# driver_3KW.net
KiCad netlist of a schematic drawn in EAGLE
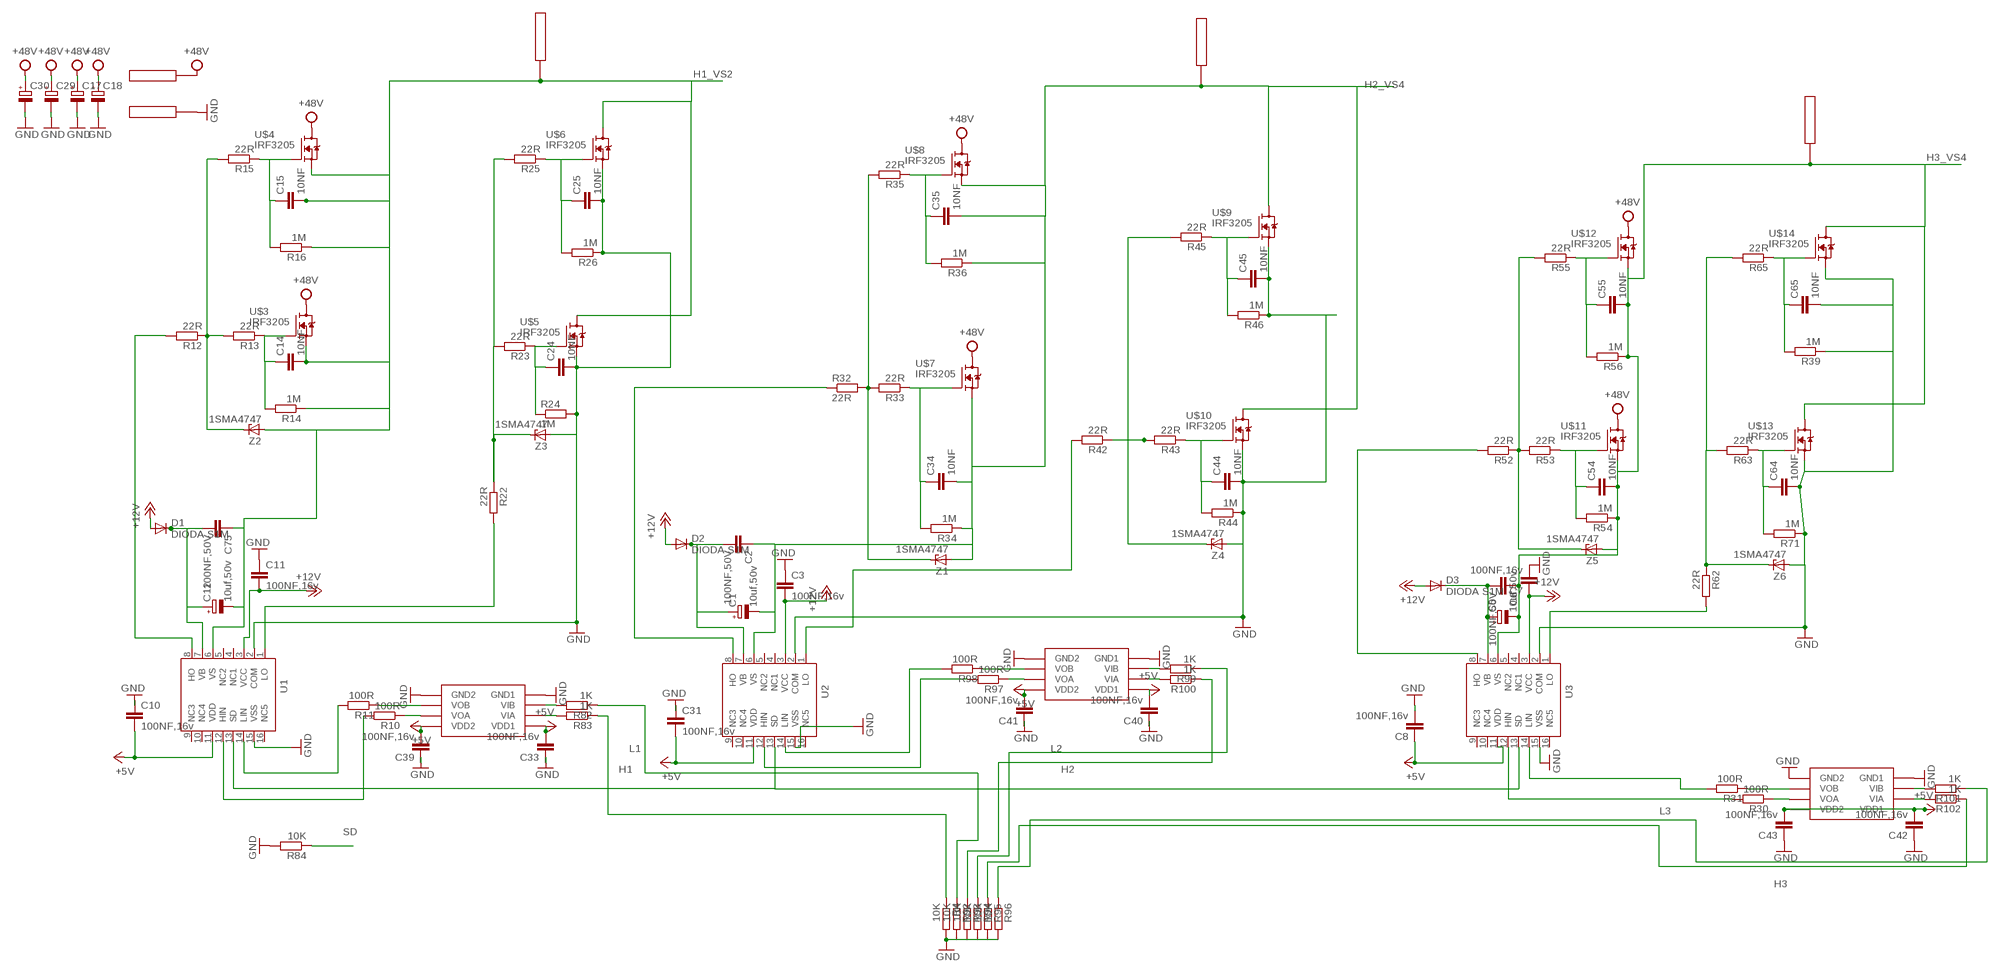
[diagram p0: schematic, sheet 1, part 1 of 2]
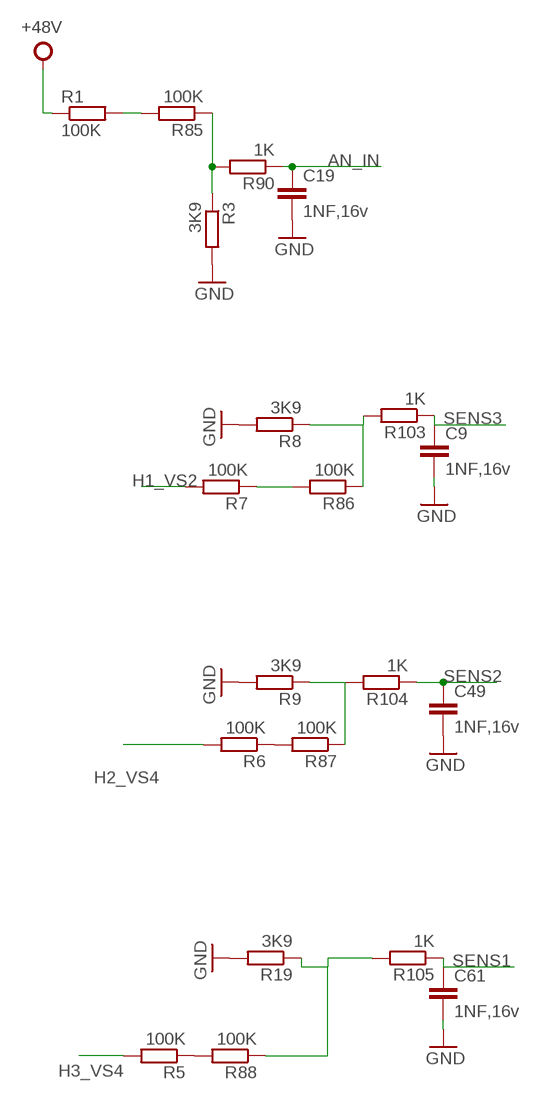
[diagram p1: schematic, sheet 1, part 2 of 2]
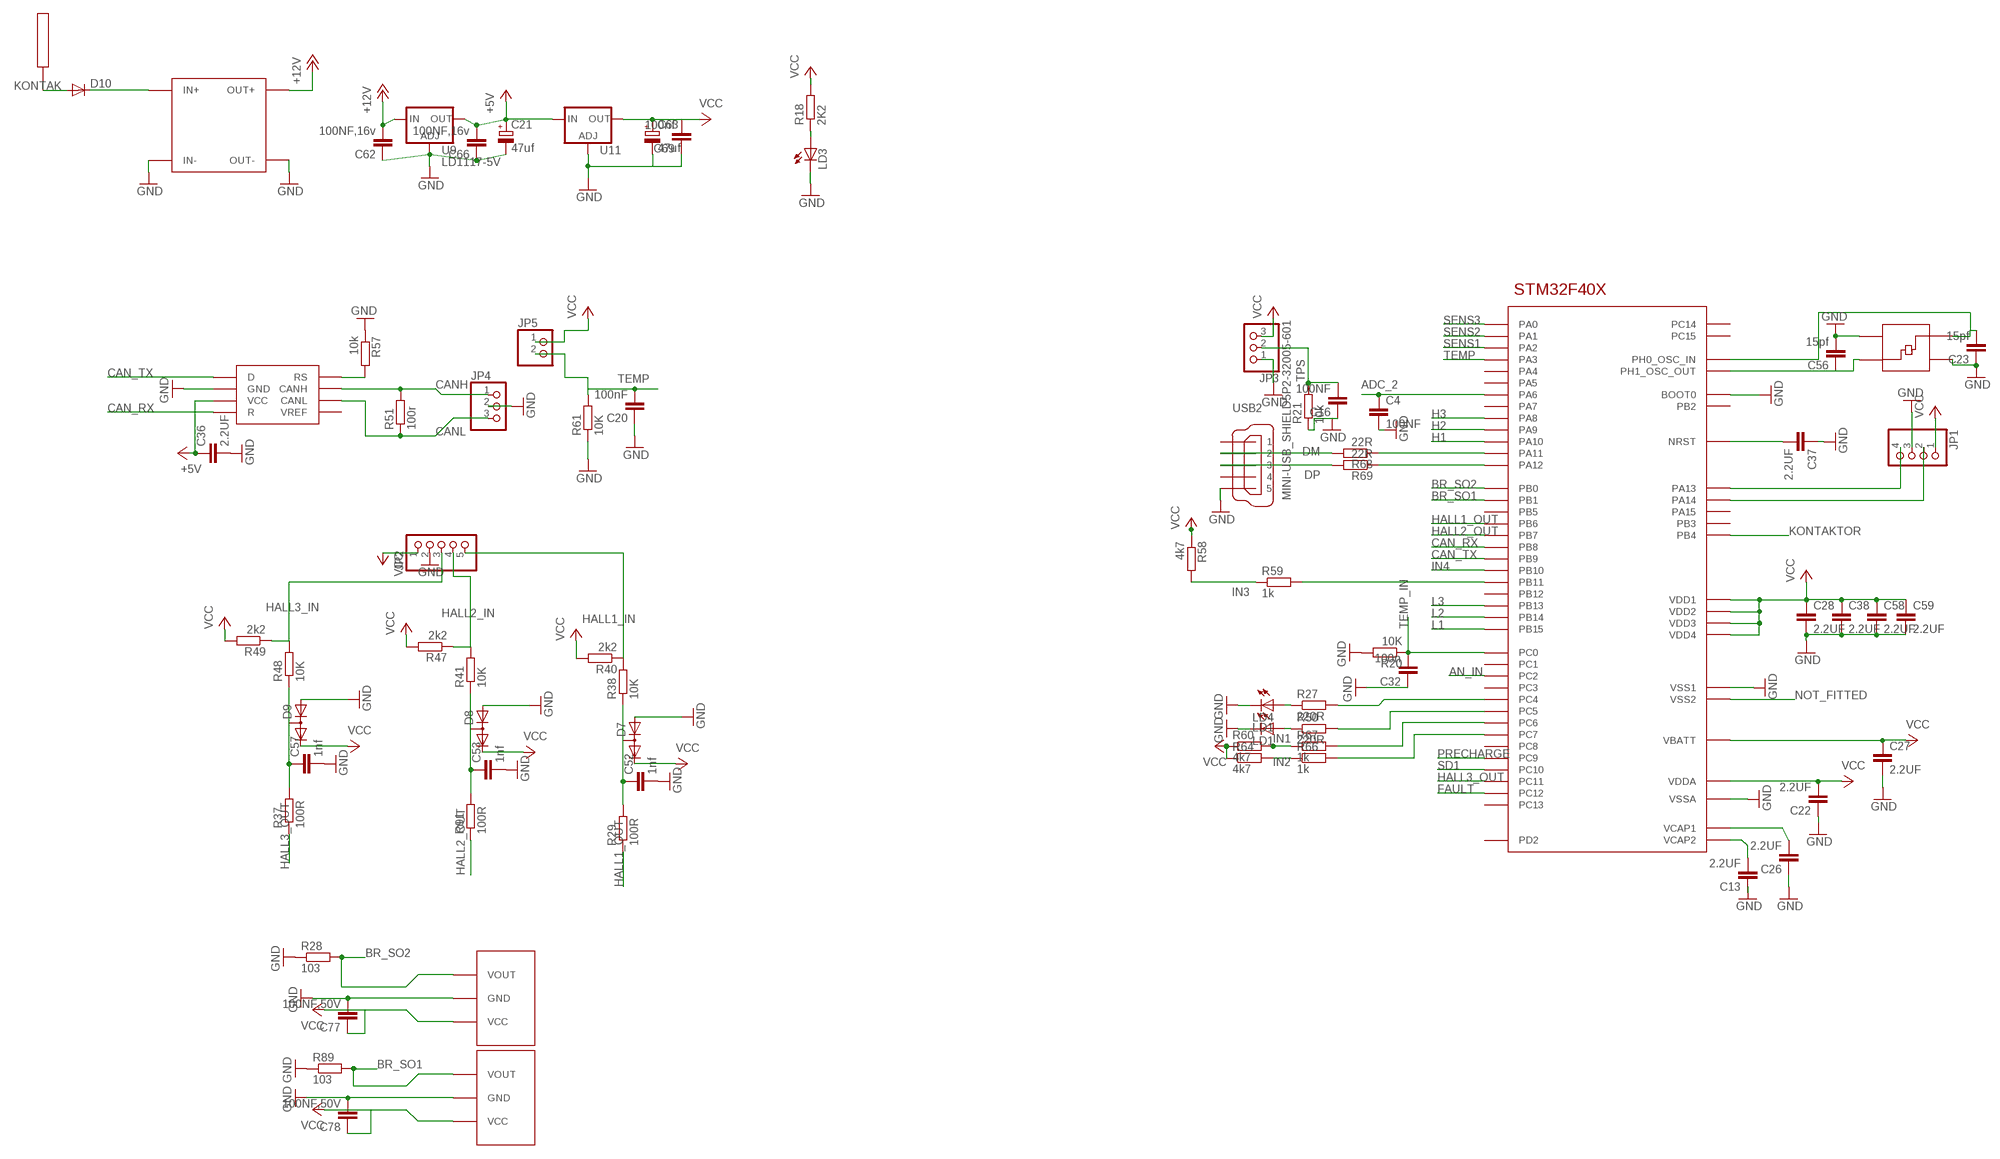
[diagram p2: schematic, sheet 2]

(export (version "E")
  (design (tool "Eeschema 10.0.6"))
  (components
    (comp (ref "C4")
      (value "100NF")
      (footprint "eagle-import:C_0805")
      (libsource (lib "eagle-import") (part "C_0805"))
    )
    (comp (ref "C13")
      (value "2.2UF")
      (footprint "eagle-import:C_0805")
      (libsource (lib "eagle-import") (part "C_0805"))
    )
    (comp (ref "C16")
      (value "100NF")
      (footprint "eagle-import:C_0805")
      (libsource (lib "eagle-import") (part "C_0805"))
    )
    (comp (ref "C20")
      (value "100nF")
      (footprint "eagle-import:C_0805")
      (libsource (lib "eagle-import") (part "C_0805"))
    )
    (comp (ref "C21")
      (value "47uf")
      (footprint "eagle-import:153CLV-0605")
      (libsource (lib "eagle-import") (part "CPOL-EU153CLV-0605"))
    )
    (comp (ref "C22")
      (value "2.2UF")
      (footprint "eagle-import:C_0805")
      (libsource (lib "eagle-import") (part "C_0805"))
    )
    (comp (ref "C23")
      (value "15pf")
      (footprint "eagle-import:C_0805")
      (libsource (lib "eagle-import") (part "C_0805"))
    )
    (comp (ref "C26")
      (value "2.2UF")
      (footprint "eagle-import:C_0805")
      (libsource (lib "eagle-import") (part "C_0805"))
    )
    (comp (ref "C27")
      (value "2.2UF")
      (footprint "eagle-import:C_0805")
      (libsource (lib "eagle-import") (part "C_0805"))
    )
    (comp (ref "C28")
      (value "2.2UF")
      (footprint "eagle-import:C_0805")
      (libsource (lib "eagle-import") (part "C_0805"))
    )
    (comp (ref "C32")
      (value "100n")
      (footprint "eagle-import:C_0805")
      (libsource (lib "eagle-import") (part "C_0805"))
    )
    (comp (ref "C36")
      (value "2.2UF")
      (footprint "eagle-import:C_0805")
      (libsource (lib "eagle-import") (part "C_0805"))
    )
    (comp (ref "C37")
      (value "2.2UF")
      (footprint "eagle-import:C_0805")
      (libsource (lib "eagle-import") (part "C_0805"))
    )
    (comp (ref "C38")
      (value "2.2UF")
      (footprint "eagle-import:C_0805")
      (libsource (lib "eagle-import") (part "C_0805"))
    )
    (comp (ref "C52")
      (value "1nf")
      (footprint "eagle-import:C_0805")
      (libsource (lib "eagle-import") (part "C_0805"))
    )
    (comp (ref "C53")
      (value "1nf")
      (footprint "eagle-import:C_0805")
      (libsource (lib "eagle-import") (part "C_0805"))
    )
    (comp (ref "C56")
      (value "15pf")
      (footprint "eagle-import:C_0805")
      (libsource (lib "eagle-import") (part "C_0805"))
    )
    (comp (ref "C57")
      (value "1nf")
      (footprint "eagle-import:C_0805")
      (libsource (lib "eagle-import") (part "C_0805"))
    )
    (comp (ref "C58")
      (value "2.2UF")
      (footprint "eagle-import:C_0805")
      (libsource (lib "eagle-import") (part "C_0805"))
    )
    (comp (ref "C59")
      (value "2.2UF")
      (footprint "eagle-import:C_0805")
      (libsource (lib "eagle-import") (part "C_0805"))
    )
    (comp (ref "C62")
      (value "100NF,16v")
      (footprint "eagle-import:C_0805")
      (libsource (lib "eagle-import") (part "C_0805"))
    )
    (comp (ref "C63")
      (value "47uf")
      (footprint "eagle-import:153CLV-0605")
      (libsource (lib "eagle-import") (part "CPOL-EU153CLV-0605"))
    )
    (comp (ref "C66")
      (value "100NF,16v")
      (footprint "eagle-import:C_0805")
      (libsource (lib "eagle-import") (part "C_0805"))
    )
    (comp (ref "C69")
      (value "100nf")
      (footprint "eagle-import:C_0805")
      (libsource (lib "eagle-import") (part "C_0805"))
    )
    (comp (ref "C77")
      (value "100NF,50V")
      (footprint "eagle-import:C_0805")
      (libsource (lib "eagle-import") (part "C_0805"))
    )
    (comp (ref "C78")
      (value "100NF,50V")
      (footprint "eagle-import:C_0805")
      (libsource (lib "eagle-import") (part "C_0805"))
    )
    (comp (ref "D7")
      (value "DIODE_2CACA-SOT23")
      (footprint "eagle-import:SOT23")
      (libsource (lib "eagle-import") (part "DIODE_2CACA-SOT23"))
    )
    (comp (ref "D8")
      (value "DIODE_2CACA-SOT23")
      (footprint "eagle-import:SOT23")
      (libsource (lib "eagle-import") (part "DIODE_2CACA-SOT23"))
    )
    (comp (ref "D9")
      (value "DIODE_2CACA-SOT23")
      (footprint "eagle-import:SOT23")
      (libsource (lib "eagle-import") (part "DIODE_2CACA-SOT23"))
    )
    (comp (ref "D10")
      (value "DIODE-SMB")
      (footprint "eagle-import:SMB")
      (libsource (lib "eagle-import") (part "DIODE-SMB"))
    )
    (comp (ref "JP1")
      (value "PINHD-1X4")
      (footprint "eagle-import:1X04")
      (libsource (lib "eagle-import") (part "PINHD-1X4"))
    )
    (comp (ref "JP2")
      (value "PINHD-1X5")
      (footprint "eagle-import:1X05")
      (libsource (lib "eagle-import") (part "PINHD-1X5"))
    )
    (comp (ref "JP3")
      (value "PINHD-1X3")
      (footprint "eagle-import:1X03")
      (libsource (lib "eagle-import") (part "PINHD-1X3"))
    )
    (comp (ref "JP4")
      (value "PINHD-1X3")
      (footprint "eagle-import:1X03")
      (libsource (lib "eagle-import") (part "PINHD-1X3"))
    )
    (comp (ref "JP5")
      (value "PINHD-1X2")
      (footprint "eagle-import:1X02")
      (libsource (lib "eagle-import") (part "PINHD-1X2"))
    )
    (comp (ref "LD1")
      (value "LED3MM")
      (footprint "eagle-import:LED3MM")
      (libsource (lib "eagle-import") (part "LED3MM"))
    )
    (comp (ref "LD3")
      (value "LED3MM")
      (footprint "eagle-import:LED3MM")
      (libsource (lib "eagle-import") (part "LED3MM"))
    )
    (comp (ref "LD4")
      (value "LD1")
      (footprint "eagle-import:LED3MM")
      (libsource (lib "eagle-import") (part "LED3MM"))
    )
    (comp (ref "R18")
      (value "2K2")
      (footprint "eagle-import:R_0805")
      (libsource (lib "eagle-import") (part "R_EU"))
    )
    (comp (ref "R20")
      (value "10K")
      (footprint "eagle-import:R_0805")
      (libsource (lib "eagle-import") (part "R_EU"))
    )
    (comp (ref "R21")
      (value "10k")
      (footprint "eagle-import:R_0805")
      (libsource (lib "eagle-import") (part "R_EU"))
    )
    (comp (ref "R27")
      (value "220R")
      (footprint "eagle-import:R_0805")
      (libsource (lib "eagle-import") (part "R_EU"))
    )
    (comp (ref "R28")
      (value "103")
      (footprint "eagle-import:R_0805")
      (libsource (lib "eagle-import") (part "R_EU"))
    )
    (comp (ref "R29")
      (value "100R")
      (footprint "eagle-import:R_0805")
      (libsource (lib "eagle-import") (part "R_EU"))
    )
    (comp (ref "R37")
      (value "100R")
      (footprint "eagle-import:R_0805")
      (libsource (lib "eagle-import") (part "R_EU"))
    )
    (comp (ref "R38")
      (value "10K")
      (footprint "eagle-import:R_0805")
      (libsource (lib "eagle-import") (part "R_EU"))
    )
    (comp (ref "R40")
      (value "2k2")
      (footprint "eagle-import:R_0805")
      (libsource (lib "eagle-import") (part "R_EU"))
    )
    (comp (ref "R41")
      (value "10K")
      (footprint "eagle-import:R_0805")
      (libsource (lib "eagle-import") (part "R_EU"))
    )
    (comp (ref "R47")
      (value "2k2")
      (footprint "eagle-import:R_0805")
      (libsource (lib "eagle-import") (part "R_EU"))
    )
    (comp (ref "R48")
      (value "10K")
      (footprint "eagle-import:R_0805")
      (libsource (lib "eagle-import") (part "R_EU"))
    )
    (comp (ref "R49")
      (value "2k2")
      (footprint "eagle-import:R_0805")
      (libsource (lib "eagle-import") (part "R_EU"))
    )
    (comp (ref "R50")
      (value "220R")
      (footprint "eagle-import:R_0805")
      (libsource (lib "eagle-import") (part "R_EU"))
    )
    (comp (ref "R51")
      (value "100r")
      (footprint "eagle-import:R_0805")
      (libsource (lib "eagle-import") (part "R_EU"))
    )
    (comp (ref "R57")
      (value "10k")
      (footprint "eagle-import:R_0805")
      (libsource (lib "eagle-import") (part "R_EU"))
    )
    (comp (ref "R58")
      (value "4k7")
      (footprint "eagle-import:R_0805")
      (libsource (lib "eagle-import") (part "R_EU"))
    )
    (comp (ref "R59")
      (value "1k")
      (footprint "eagle-import:R_0805")
      (libsource (lib "eagle-import") (part "R_EU"))
    )
    (comp (ref "R60")
      (value "4k7")
      (footprint "eagle-import:R_0805")
      (libsource (lib "eagle-import") (part "R_EU"))
    )
    (comp (ref "R61")
      (value "10K")
      (footprint "eagle-import:R_0805")
      (libsource (lib "eagle-import") (part "R_EU"))
    )
    (comp (ref "R64")
      (value "4k7")
      (footprint "eagle-import:R_0805")
      (libsource (lib "eagle-import") (part "R_EU"))
    )
    (comp (ref "R66")
      (value "1k")
      (footprint "eagle-import:R_0805")
      (libsource (lib "eagle-import") (part "R_EU"))
    )
    (comp (ref "R67")
      (value "1k")
      (footprint "eagle-import:R_0805")
      (libsource (lib "eagle-import") (part "R_EU"))
    )
    (comp (ref "R68")
      (value "22R")
      (footprint "eagle-import:R_0805")
      (libsource (lib "eagle-import") (part "R_EU"))
    )
    (comp (ref "R69")
      (value "22R")
      (footprint "eagle-import:R_0805")
      (libsource (lib "eagle-import") (part "R_EU"))
    )
    (comp (ref "R89")
      (value "103")
      (footprint "eagle-import:R_0805")
      (libsource (lib "eagle-import") (part "R_EU"))
    )
    (comp (ref "R91")
      (value "100R")
      (footprint "eagle-import:R_0805")
      (libsource (lib "eagle-import") (part "R_EU"))
    )
    (comp (ref "U$1")
      (value "LM2596")
      (footprint "eagle-import:DC-DC")
      (libsource (lib "eagle-import") (part "LM2596"))
    )
    (comp (ref "U$2")
      (value "STM32F40X")
      (footprint "eagle-import:DIP64")
      (libsource (lib "eagle-import") (part "STM32F40X"))
    )
    (comp (ref "U$20")
      (value "L01Z400S05")
      (footprint "eagle-import:L01ZXXXS05")
      (libsource (lib "eagle-import") (part "L01Z400S05"))
    )
    (comp (ref "U$21")
      (value "L01Z400S05")
      (footprint "eagle-import:L01ZXXXS05")
      (libsource (lib "eagle-import") (part "L01Z400S05"))
    )
    (comp (ref "U$22")
      (value "PINOUT")
      (footprint "eagle-import:1DIP")
      (libsource (lib "eagle-import") (part "PINOUT"))
    )
    (comp (ref "U9")
      (value "LD1117-5V")
      (footprint "eagle-import:DPACK@1")
      (libsource (lib "eagle-import") (part "v-reg_LM317?MABDT"))
    )
    (comp (ref "U11")
      (value "LM317MABDT")
      (footprint "eagle-import:DPACK@1")
      (libsource (lib "eagle-import") (part "v-reg_LM317?MABDT"))
    )
    (comp (ref "U73")
      (value "MCP2551")
      (footprint "eagle-import:SN65HVD230")
      (libsource (lib "eagle-import") (part "SN65HVD230"))
    )
    (comp (ref "USB2")
      (value "MINI-USB_SHIELD5P2-32005-601")
      (footprint "eagle-import:32005-601")
      (libsource (lib "eagle-import") (part "MINI-USB_SHIELD5P2-32005-601"))
    )
    (comp (ref "X2")
      (value "UBM")
      (footprint "eagle-import:UBM")
      (libsource (lib "eagle-import") (part "UBM"))
    )
    (comp (ref "C1")
      (value "10uf,50v")
      (footprint "eagle-import:E2,5-5")
      (libsource (lib "eagle-import") (part "CPOL-EUE2.5-5"))
    )
    (comp (ref "C2")
      (value "100NF,50V")
      (footprint "eagle-import:C_0805")
      (libsource (lib "eagle-import") (part "C_0805"))
    )
    (comp (ref "C3")
      (value "100NF,16v")
      (footprint "eagle-import:C_0805")
      (libsource (lib "eagle-import") (part "C_0805"))
    )
    (comp (ref "C5")
      (value "10uf,50v")
      (footprint "eagle-import:E2,5-5")
      (libsource (lib "eagle-import") (part "CPOL-EUE2.5-5"))
    )
    (comp (ref "C6")
      (value "100NF,50V")
      (footprint "eagle-import:C_0805")
      (libsource (lib "eagle-import") (part "C_0805"))
    )
    (comp (ref "C7")
      (value "100NF,16v")
      (footprint "eagle-import:C_0805")
      (libsource (lib "eagle-import") (part "C_0805"))
    )
    (comp (ref "C8")
      (value "100NF,16v")
      (footprint "eagle-import:C_0805")
      (libsource (lib "eagle-import") (part "C_0805"))
    )
    (comp (ref "C9")
      (value "1NF,16v")
      (footprint "eagle-import:C_0805")
      (libsource (lib "eagle-import") (part "C_0805"))
    )
    (comp (ref "C10")
      (value "100NF,16v")
      (footprint "eagle-import:C_0805")
      (libsource (lib "eagle-import") (part "C_0805"))
    )
    (comp (ref "C11")
      (value "100NF,16v")
      (footprint "eagle-import:C_0805")
      (libsource (lib "eagle-import") (part "C_0805"))
    )
    (comp (ref "C12")
      (value "10uf,50v")
      (footprint "eagle-import:E2,5-5")
      (libsource (lib "eagle-import") (part "CPOL-EUE2.5-5"))
    )
    (comp (ref "C14")
      (value "10NF")
      (footprint "eagle-import:C_0805")
      (libsource (lib "eagle-import") (part "C_0805"))
    )
    (comp (ref "C15")
      (value "10NF")
      (footprint "eagle-import:C_0805")
      (libsource (lib "eagle-import") (part "C_0805"))
    )
    (comp (ref "C17")
      (value "CPOL-EUE7.5-16")
      (footprint "eagle-import:E7,5-16")
      (libsource (lib "eagle-import") (part "CPOL-EUE7.5-16"))
    )
    (comp (ref "C18")
      (value "CPOL-EUE7.5-16")
      (footprint "eagle-import:E7,5-16")
      (libsource (lib "eagle-import") (part "CPOL-EUE7.5-16"))
    )
    (comp (ref "C19")
      (value "1NF,16v")
      (footprint "eagle-import:C_0805")
      (libsource (lib "eagle-import") (part "C_0805"))
    )
    (comp (ref "C24")
      (value "10NF")
      (footprint "eagle-import:C_0805")
      (libsource (lib "eagle-import") (part "C_0805"))
    )
    (comp (ref "C25")
      (value "10NF")
      (footprint "eagle-import:C_0805")
      (libsource (lib "eagle-import") (part "C_0805"))
    )
    (comp (ref "C29")
      (value "CPOL-EUE7.5-16")
      (footprint "eagle-import:E7,5-16")
      (libsource (lib "eagle-import") (part "CPOL-EUE7.5-16"))
    )
    (comp (ref "C30")
      (value "CPOL-EUE7.5-16")
      (footprint "eagle-import:E7,5-16")
      (libsource (lib "eagle-import") (part "CPOL-EUE7.5-16"))
    )
    (comp (ref "C31")
      (value "100NF,16v")
      (footprint "eagle-import:C_0805")
      (libsource (lib "eagle-import") (part "C_0805"))
    )
    (comp (ref "C33")
      (value "100NF,16v")
      (footprint "eagle-import:C_0805")
      (libsource (lib "eagle-import") (part "C_0805"))
    )
    (comp (ref "C34")
      (value "10NF")
      (footprint "eagle-import:C_0805")
      (libsource (lib "eagle-import") (part "C_0805"))
    )
    (comp (ref "C35")
      (value "10NF")
      (footprint "eagle-import:C_0805")
      (libsource (lib "eagle-import") (part "C_0805"))
    )
    (comp (ref "C39")
      (value "100NF,16v")
      (footprint "eagle-import:C_0805")
      (libsource (lib "eagle-import") (part "C_0805"))
    )
    (comp (ref "C40")
      (value "100NF,16v")
      (footprint "eagle-import:C_0805")
      (libsource (lib "eagle-import") (part "C_0805"))
    )
    (comp (ref "C41")
      (value "100NF,16v")
      (footprint "eagle-import:C_0805")
      (libsource (lib "eagle-import") (part "C_0805"))
    )
    (comp (ref "C42")
      (value "100NF,16v")
      (footprint "eagle-import:C_0805")
      (libsource (lib "eagle-import") (part "C_0805"))
    )
    (comp (ref "C43")
      (value "100NF,16v")
      (footprint "eagle-import:C_0805")
      (libsource (lib "eagle-import") (part "C_0805"))
    )
    (comp (ref "C44")
      (value "10NF")
      (footprint "eagle-import:C_0805")
      (libsource (lib "eagle-import") (part "C_0805"))
    )
    (comp (ref "C45")
      (value "10NF")
      (footprint "eagle-import:C_0805")
      (libsource (lib "eagle-import") (part "C_0805"))
    )
    (comp (ref "C49")
      (value "1NF,16v")
      (footprint "eagle-import:C_0805")
      (libsource (lib "eagle-import") (part "C_0805"))
    )
    (comp (ref "C54")
      (value "10NF")
      (footprint "eagle-import:C_0805")
      (libsource (lib "eagle-import") (part "C_0805"))
    )
    (comp (ref "C55")
      (value "10NF")
      (footprint "eagle-import:C_0805")
      (libsource (lib "eagle-import") (part "C_0805"))
    )
    (comp (ref "C61")
      (value "1NF,16v")
      (footprint "eagle-import:C_0805")
      (libsource (lib "eagle-import") (part "C_0805"))
    )
    (comp (ref "C64")
      (value "10NF")
      (footprint "eagle-import:C_0805")
      (libsource (lib "eagle-import") (part "C_0805"))
    )
    (comp (ref "C65")
      (value "10NF")
      (footprint "eagle-import:C_0805")
      (libsource (lib "eagle-import") (part "C_0805"))
    )
    (comp (ref "C75")
      (value "100NF,50V")
      (footprint "eagle-import:C_0805")
      (libsource (lib "eagle-import") (part "C_0805"))
    )
    (comp (ref "D1")
      (value "DIODA S1M")
      (footprint "eagle-import:DO-214AC")
      (libsource (lib "eagle-import") (part "DIODE-DO-214AC"))
    )
    (comp (ref "D2")
      (value "DIODA S1M")
      (footprint "eagle-import:DO-214AC")
      (libsource (lib "eagle-import") (part "DIODE-DO-214AC"))
    )
    (comp (ref "D3")
      (value "DIODA S1M")
      (footprint "eagle-import:DO-214AC")
      (libsource (lib "eagle-import") (part "DIODE-DO-214AC"))
    )
    (comp (ref "R1")
      (value "100K")
      (footprint "eagle-import:1206X")
      (libsource (lib "eagle-import") (part "R-EU_R1206X"))
    )
    (comp (ref "R3")
      (value "3K9")
      (footprint "eagle-import:1206X")
      (libsource (lib "eagle-import") (part "R-EU_R1206X"))
    )
    (comp (ref "R4")
      (value "10K")
      (footprint "eagle-import:R_0805")
      (libsource (lib "eagle-import") (part "R_EU"))
    )
    (comp (ref "R5")
      (value "100K")
      (footprint "eagle-import:1206X")
      (libsource (lib "eagle-import") (part "R-EU_R1206X"))
    )
    (comp (ref "R6")
      (value "100K")
      (footprint "eagle-import:1206X")
      (libsource (lib "eagle-import") (part "R-EU_R1206X"))
    )
    (comp (ref "R7")
      (value "100K")
      (footprint "eagle-import:1206X")
      (libsource (lib "eagle-import") (part "R-EU_R1206X"))
    )
    (comp (ref "R8")
      (value "3K9")
      (footprint "eagle-import:1206X")
      (libsource (lib "eagle-import") (part "R-EU_R1206X"))
    )
    (comp (ref "R9")
      (value "3K9")
      (footprint "eagle-import:1206X")
      (libsource (lib "eagle-import") (part "R-EU_R1206X"))
    )
    (comp (ref "R10")
      (value "100R")
      (footprint "eagle-import:R_0805")
      (libsource (lib "eagle-import") (part "R_EU"))
    )
    (comp (ref "R11")
      (value "100R")
      (footprint "eagle-import:R_0805")
      (libsource (lib "eagle-import") (part "R_EU"))
    )
    (comp (ref "R12")
      (value "22R")
      (footprint "eagle-import:1210X")
      (libsource (lib "eagle-import") (part "R-EU_1210X"))
    )
    (comp (ref "R13")
      (value "22R")
      (footprint "eagle-import:1210X")
      (libsource (lib "eagle-import") (part "R-EU_1210X"))
    )
    (comp (ref "R14")
      (value "1M")
      (footprint "eagle-import:1206X")
      (libsource (lib "eagle-import") (part "R-EU_R1206X"))
    )
    (comp (ref "R15")
      (value "22R")
      (footprint "eagle-import:1210X")
      (libsource (lib "eagle-import") (part "R-EU_1210X"))
    )
    (comp (ref "R16")
      (value "1M")
      (footprint "eagle-import:1206X")
      (libsource (lib "eagle-import") (part "R-EU_R1206X"))
    )
    (comp (ref "R19")
      (value "3K9")
      (footprint "eagle-import:1206X")
      (libsource (lib "eagle-import") (part "R-EU_R1206X"))
    )
    (comp (ref "R22")
      (value "22R")
      (footprint "eagle-import:1210X")
      (libsource (lib "eagle-import") (part "R-EU_1210X"))
    )
    (comp (ref "R23")
      (value "22R")
      (footprint "eagle-import:1210X")
      (libsource (lib "eagle-import") (part "R-EU_1210X"))
    )
    (comp (ref "R24")
      (value "1M")
      (footprint "eagle-import:1206X")
      (libsource (lib "eagle-import") (part "R-EU_R1206X"))
    )
    (comp (ref "R25")
      (value "22R")
      (footprint "eagle-import:1210X")
      (libsource (lib "eagle-import") (part "R-EU_1210X"))
    )
    (comp (ref "R26")
      (value "1M")
      (footprint "eagle-import:1206X")
      (libsource (lib "eagle-import") (part "R-EU_R1206X"))
    )
    (comp (ref "R30")
      (value "100R")
      (footprint "eagle-import:R_0805")
      (libsource (lib "eagle-import") (part "R_EU"))
    )
    (comp (ref "R31")
      (value "100R")
      (footprint "eagle-import:R_0805")
      (libsource (lib "eagle-import") (part "R_EU"))
    )
    (comp (ref "R32")
      (value "22R")
      (footprint "eagle-import:1210X")
      (libsource (lib "eagle-import") (part "R-EU_1210X"))
    )
    (comp (ref "R33")
      (value "22R")
      (footprint "eagle-import:1210X")
      (libsource (lib "eagle-import") (part "R-EU_1210X"))
    )
    (comp (ref "R34")
      (value "1M")
      (footprint "eagle-import:1206X")
      (libsource (lib "eagle-import") (part "R-EU_R1206X"))
    )
    (comp (ref "R35")
      (value "22R")
      (footprint "eagle-import:1210X")
      (libsource (lib "eagle-import") (part "R-EU_1210X"))
    )
    (comp (ref "R36")
      (value "1M")
      (footprint "eagle-import:1206X")
      (libsource (lib "eagle-import") (part "R-EU_R1206X"))
    )
    (comp (ref "R39")
      (value "1M")
      (footprint "eagle-import:1206X")
      (libsource (lib "eagle-import") (part "R-EU_R1206X"))
    )
    (comp (ref "R42")
      (value "22R")
      (footprint "eagle-import:1210X")
      (libsource (lib "eagle-import") (part "R-EU_1210X"))
    )
    (comp (ref "R43")
      (value "22R")
      (footprint "eagle-import:1210X")
      (libsource (lib "eagle-import") (part "R-EU_1210X"))
    )
    (comp (ref "R44")
      (value "1M")
      (footprint "eagle-import:1206X")
      (libsource (lib "eagle-import") (part "R-EU_R1206X"))
    )
    (comp (ref "R45")
      (value "22R")
      (footprint "eagle-import:1210X")
      (libsource (lib "eagle-import") (part "R-EU_1210X"))
    )
    (comp (ref "R46")
      (value "1M")
      (footprint "eagle-import:1206X")
      (libsource (lib "eagle-import") (part "R-EU_R1206X"))
    )
    (comp (ref "R52")
      (value "22R")
      (footprint "eagle-import:1210X")
      (libsource (lib "eagle-import") (part "R-EU_1210X"))
    )
    (comp (ref "R53")
      (value "22R")
      (footprint "eagle-import:1210X")
      (libsource (lib "eagle-import") (part "R-EU_1210X"))
    )
    (comp (ref "R54")
      (value "1M")
      (footprint "eagle-import:1206X")
      (libsource (lib "eagle-import") (part "R-EU_R1206X"))
    )
    (comp (ref "R55")
      (value "22R")
      (footprint "eagle-import:1210X")
      (libsource (lib "eagle-import") (part "R-EU_1210X"))
    )
    (comp (ref "R56")
      (value "1M")
      (footprint "eagle-import:1206X")
      (libsource (lib "eagle-import") (part "R-EU_R1206X"))
    )
    (comp (ref "R62")
      (value "22R")
      (footprint "eagle-import:1210X")
      (libsource (lib "eagle-import") (part "R-EU_1210X"))
    )
    (comp (ref "R63")
      (value "22R")
      (footprint "eagle-import:1210X")
      (libsource (lib "eagle-import") (part "R-EU_1210X"))
    )
    (comp (ref "R65")
      (value "22R")
      (footprint "eagle-import:1210X")
      (libsource (lib "eagle-import") (part "R-EU_1210X"))
    )
    (comp (ref "R71")
      (value "1M")
      (footprint "eagle-import:1206X")
      (libsource (lib "eagle-import") (part "R-EU_R1206X"))
    )
    (comp (ref "R82")
      (value "1K")
      (footprint "eagle-import:R_0805")
      (libsource (lib "eagle-import") (part "R_EU"))
    )
    (comp (ref "R83")
      (value "1K")
      (footprint "eagle-import:R_0805")
      (libsource (lib "eagle-import") (part "R_EU"))
    )
    (comp (ref "R84")
      (value "10K")
      (footprint "eagle-import:R_0805")
      (libsource (lib "eagle-import") (part "R_EU"))
    )
    (comp (ref "R85")
      (value "100K")
      (footprint "eagle-import:1206X")
      (libsource (lib "eagle-import") (part "R-EU_R1206X"))
    )
    (comp (ref "R86")
      (value "100K")
      (footprint "eagle-import:1206X")
      (libsource (lib "eagle-import") (part "R-EU_R1206X"))
    )
    (comp (ref "R87")
      (value "100K")
      (footprint "eagle-import:1206X")
      (libsource (lib "eagle-import") (part "R-EU_R1206X"))
    )
    (comp (ref "R88")
      (value "100K")
      (footprint "eagle-import:1206X")
      (libsource (lib "eagle-import") (part "R-EU_R1206X"))
    )
    (comp (ref "R90")
      (value "1K")
      (footprint "eagle-import:1206X")
      (libsource (lib "eagle-import") (part "R-EU_R1206X"))
    )
    (comp (ref "R92")
      (value "10K")
      (footprint "eagle-import:R_0805")
      (libsource (lib "eagle-import") (part "R_EU"))
    )
    (comp (ref "R93")
      (value "10K")
      (footprint "eagle-import:R_0805")
      (libsource (lib "eagle-import") (part "R_EU"))
    )
    (comp (ref "R94")
      (value "10K")
      (footprint "eagle-import:R_0805")
      (libsource (lib "eagle-import") (part "R_EU"))
    )
    (comp (ref "R95")
      (value "10K")
      (footprint "eagle-import:R_0805")
      (libsource (lib "eagle-import") (part "R_EU"))
    )
    (comp (ref "R96")
      (value "10K")
      (footprint "eagle-import:R_0805")
      (libsource (lib "eagle-import") (part "R_EU"))
    )
    (comp (ref "R97")
      (value "100R")
      (footprint "eagle-import:R_0805")
      (libsource (lib "eagle-import") (part "R_EU"))
    )
    (comp (ref "R98")
      (value "100R")
      (footprint "eagle-import:R_0805")
      (libsource (lib "eagle-import") (part "R_EU"))
    )
    (comp (ref "R99")
      (value "1K")
      (footprint "eagle-import:R_0805")
      (libsource (lib "eagle-import") (part "R_EU"))
    )
    (comp (ref "R100")
      (value "1K")
      (footprint "eagle-import:R_0805")
      (libsource (lib "eagle-import") (part "R_EU"))
    )
    (comp (ref "R101")
      (value "1K")
      (footprint "eagle-import:R_0805")
      (libsource (lib "eagle-import") (part "R_EU"))
    )
    (comp (ref "R102")
      (value "1K")
      (footprint "eagle-import:R_0805")
      (libsource (lib "eagle-import") (part "R_EU"))
    )
    (comp (ref "R103")
      (value "1K")
      (footprint "eagle-import:1206X")
      (libsource (lib "eagle-import") (part "R-EU_R1206X"))
    )
    (comp (ref "R104")
      (value "1K")
      (footprint "eagle-import:1206X")
      (libsource (lib "eagle-import") (part "R-EU_R1206X"))
    )
    (comp (ref "R105")
      (value "1K")
      (footprint "eagle-import:1206X")
      (libsource (lib "eagle-import") (part "R-EU_R1206X"))
    )
    (comp (ref "U$3")
      (value "IRF3205")
      (footprint "eagle-import:TO220AB")
      (libsource (lib "eagle-import") (part "IRF3205"))
    )
    (comp (ref "U$4")
      (value "IRF3205")
      (footprint "eagle-import:TO220AB")
      (libsource (lib "eagle-import") (part "IRF3205"))
    )
    (comp (ref "U$5")
      (value "IRF3205")
      (footprint "eagle-import:TO220AB")
      (libsource (lib "eagle-import") (part "IRF3205"))
    )
    (comp (ref "U$6")
      (value "IRF3205")
      (footprint "eagle-import:TO220AB")
      (libsource (lib "eagle-import") (part "IRF3205"))
    )
    (comp (ref "U$7")
      (value "IRF3205")
      (footprint "eagle-import:TO220AB")
      (libsource (lib "eagle-import") (part "IRF3205"))
    )
    (comp (ref "U$8")
      (value "IRF3205")
      (footprint "eagle-import:TO220AB")
      (libsource (lib "eagle-import") (part "IRF3205"))
    )
    (comp (ref "U$9")
      (value "IRF3205")
      (footprint "eagle-import:TO220AB")
      (libsource (lib "eagle-import") (part "IRF3205"))
    )
    (comp (ref "U$10")
      (value "IRF3205")
      (footprint "eagle-import:TO220AB")
      (libsource (lib "eagle-import") (part "IRF3205"))
    )
    (comp (ref "U$11")
      (value "IRF3205")
      (footprint "eagle-import:TO220AB")
      (libsource (lib "eagle-import") (part "IRF3205"))
    )
    (comp (ref "U$12")
      (value "IRF3205")
      (footprint "eagle-import:TO220AB")
      (libsource (lib "eagle-import") (part "IRF3205"))
    )
    (comp (ref "U$13")
      (value "IRF3205")
      (footprint "eagle-import:TO220AB")
      (libsource (lib "eagle-import") (part "IRF3205"))
    )
    (comp (ref "U$14")
      (value "IRF3205")
      (footprint "eagle-import:TO220AB")
      (libsource (lib "eagle-import") (part "IRF3205"))
    )
    (comp (ref "U$15")
      (value "PINOUT")
      (footprint "eagle-import:1DIP")
      (libsource (lib "eagle-import") (part "PINOUT"))
    )
    (comp (ref "U$16")
      (value "PINOUT")
      (footprint "eagle-import:1DIP")
      (libsource (lib "eagle-import") (part "PINOUT"))
    )
    (comp (ref "U$17")
      (value "PINOUT")
      (footprint "eagle-import:1DIP")
      (libsource (lib "eagle-import") (part "PINOUT"))
    )
    (comp (ref "U$18")
      (value "PINOUT")
      (footprint "eagle-import:1DIP")
      (libsource (lib "eagle-import") (part "PINOUT"))
    )
    (comp (ref "U$19")
      (value "PINOUT")
      (footprint "eagle-import:1DIP")
      (libsource (lib "eagle-import") (part "PINOUT"))
    )
    (comp (ref "U1")
      (value "IRS2110")
      (footprint "eagle-import:SO16L")
      (libsource (lib "eagle-import") (part "MAX304WE3C"))
    )
    (comp (ref "U2")
      (value "IRS2110")
      (footprint "eagle-import:SO16L")
      (libsource (lib "eagle-import") (part "MAX304WE3C"))
    )
    (comp (ref "U3")
      (value "IRS2110")
      (footprint "eagle-import:SO16L")
      (libsource (lib "eagle-import") (part "MAX304WE3C"))
    )
    (comp (ref "U4")
      (value "ADUM1200")
      (footprint "eagle-import:SO8")
      (libsource (lib "eagle-import") (part "ADUM1200"))
    )
    (comp (ref "U5")
      (value "ADUM1200")
      (footprint "eagle-import:SO8")
      (libsource (lib "eagle-import") (part "ADUM1200"))
    )
    (comp (ref "U6")
      (value "ADUM1200")
      (footprint "eagle-import:SO8")
      (libsource (lib "eagle-import") (part "ADUM1200"))
    )
    (comp (ref "Z1")
      (value "1SMA4747")
      (footprint "eagle-import:SOD80C@1")
      (libsource (lib "eagle-import") (part "ZENER-DIODESOD80C"))
    )
    (comp (ref "Z2")
      (value "1SMA4747")
      (footprint "eagle-import:SOD80C@1")
      (libsource (lib "eagle-import") (part "ZENER-DIODESOD80C"))
    )
    (comp (ref "Z3")
      (value "1SMA4747")
      (footprint "eagle-import:SOD80C@1")
      (libsource (lib "eagle-import") (part "ZENER-DIODESOD80C"))
    )
    (comp (ref "Z4")
      (value "1SMA4747")
      (footprint "eagle-import:SOD80C@1")
      (libsource (lib "eagle-import") (part "ZENER-DIODESOD80C"))
    )
    (comp (ref "Z5")
      (value "1SMA4747")
      (footprint "eagle-import:SOD80C@1")
      (libsource (lib "eagle-import") (part "ZENER-DIODESOD80C"))
    )
    (comp (ref "Z6")
      (value "1SMA4747")
      (footprint "eagle-import:SOD80C@1")
      (libsource (lib "eagle-import") (part "ZENER-DIODESOD80C"))
    )
  )
  (nets
    (net (code "1") (name "+5V") (class "Default")
      (node (ref "C10") (pin "2") (pinfunction "2_2") (pintype "passive"))
      (node (ref "C21") (pin "+") (pinfunction "+_+") (pintype "passive"))
      (node (ref "C31") (pin "2") (pinfunction "2_2") (pintype "passive"))
      (node (ref "C33") (pin "2") (pinfunction "2_2") (pintype "passive"))
      (node (ref "C36") (pin "1") (pinfunction "1_1") (pintype "passive"))
      (node (ref "C39") (pin "2") (pinfunction "2_2") (pintype "passive"))
      (node (ref "C40") (pin "2") (pinfunction "2_2") (pintype "passive"))
      (node (ref "C41") (pin "2") (pinfunction "2_2") (pintype "passive"))
      (node (ref "C42") (pin "2") (pinfunction "2_2") (pintype "passive"))
      (node (ref "C43") (pin "2") (pinfunction "2_2") (pintype "passive"))
      (node (ref "C66") (pin "2") (pinfunction "2_2") (pintype "passive"))
      (node (ref "C8") (pin "1") (pinfunction "1_1") (pintype "passive"))
      (node (ref "U1") (pin "11") (pinfunction "VDD_11") (pintype "output"))
      (node (ref "U11") (pin "3") (pinfunction "IN_3") (pintype "input"))
      (node (ref "U2") (pin "11") (pinfunction "VDD_11") (pintype "output"))
      (node (ref "U3") (pin "11") (pinfunction "VDD_11") (pintype "output"))
      (node (ref "U4") (pin "1") (pinfunction "VDD1_1") (pintype "bidirectional"))
      (node (ref "U4") (pin "8") (pinfunction "VDD2_8") (pintype "bidirectional"))
      (node (ref "U5") (pin "1") (pinfunction "VDD1_1") (pintype "bidirectional"))
      (node (ref "U5") (pin "8") (pinfunction "VDD2_8") (pintype "bidirectional"))
      (node (ref "U6") (pin "1") (pinfunction "VDD1_1") (pintype "bidirectional"))
      (node (ref "U6") (pin "8") (pinfunction "VDD2_8") (pintype "bidirectional"))
      (node (ref "U73") (pin "P$3") (pinfunction "VCC_P$3") (pintype "bidirectional"))
      (node (ref "U9") (pin "4") (pinfunction "OUT_4") (pintype "passive"))
    )
    (net (code "2") (name "+12V") (class "Default")
      (node (ref "C11") (pin "2") (pinfunction "2_2") (pintype "passive"))
      (node (ref "C3") (pin "2") (pinfunction "2_2") (pintype "passive"))
      (node (ref "C62") (pin "2") (pinfunction "2_2") (pintype "passive"))
      (node (ref "C7") (pin "1") (pinfunction "1_1") (pintype "passive"))
      (node (ref "D1") (pin "A") (pinfunction "A_A") (pintype "passive"))
      (node (ref "D2") (pin "A") (pinfunction "A_A") (pintype "passive"))
      (node (ref "D3") (pin "A") (pinfunction "A_A") (pintype "passive"))
      (node (ref "U$1") (pin "OUT+") (pinfunction "OUT+_OUT+") (pintype "bidirectional"))
      (node (ref "U1") (pin "3") (pinfunction "VCC_3") (pintype "output"))
      (node (ref "U2") (pin "3") (pinfunction "VCC_3") (pintype "output"))
      (node (ref "U3") (pin "3") (pinfunction "VCC_3") (pintype "output"))
      (node (ref "U9") (pin "3") (pinfunction "IN_3") (pintype "input"))
    )
    (net (code "3") (name "+48V") (class "Default")
      (node (ref "C17") (pin "+") (pinfunction "+_+") (pintype "passive"))
      (node (ref "C18") (pin "+") (pinfunction "+_+") (pintype "passive"))
      (node (ref "C29") (pin "+") (pinfunction "+_+") (pintype "passive"))
      (node (ref "C30") (pin "+") (pinfunction "+_+") (pintype "passive"))
      (node (ref "R1") (pin "P$1") (pinfunction "1_P$1") (pintype "passive"))
      (node (ref "U$11") (pin "D") (pinfunction "D_D") (pintype "passive"))
      (node (ref "U$12") (pin "D") (pinfunction "D_D") (pintype "passive"))
      (node (ref "U$18") (pin "P$1") (pinfunction "P$1_P$1") (pintype "bidirectional"))
      (node (ref "U$3") (pin "D") (pinfunction "D_D") (pintype "passive"))
      (node (ref "U$4") (pin "D") (pinfunction "D_D") (pintype "passive"))
      (node (ref "U$7") (pin "D") (pinfunction "D_D") (pintype "passive"))
      (node (ref "U$8") (pin "D") (pinfunction "D_D") (pintype "passive"))
    )
    (net (code "4") (name "ADC_2") (class "Default")
      (node (ref "C4") (pin "1") (pinfunction "1_1") (pintype "passive"))
      (node (ref "U$2") (pin "P$31") (pinfunction "PA6_P$31") (pintype "bidirectional"))
    )
    (net (code "5") (name "AN_IN") (class "Default")
      (node (ref "C19") (pin "1") (pinfunction "1_1") (pintype "passive"))
      (node (ref "R90") (pin "P$1") (pinfunction "1_P$1") (pintype "passive"))
      (node (ref "U$2") (pin "P$10") (pinfunction "PC2_P$10") (pintype "bidirectional"))
    )
    (net (code "6") (name "BR_SO1") (class "Default")
      (node (ref "R89") (pin "2") (pinfunction "2_2") (pintype "passive"))
      (node (ref "U$2") (pin "P$36") (pinfunction "PB1_P$36") (pintype "bidirectional"))
      (node (ref "U$21") (pin "1") (pinfunction "VOUT_1") (pintype "bidirectional"))
    )
    (net (code "7") (name "BR_SO2") (class "Default")
      (node (ref "R28") (pin "2") (pinfunction "2_2") (pintype "passive"))
      (node (ref "U$2") (pin "P$35") (pinfunction "PB0_P$35") (pintype "bidirectional"))
      (node (ref "U$20") (pin "1") (pinfunction "VOUT_1") (pintype "bidirectional"))
    )
    (net (code "8") (name "CANH") (class "Default")
      (node (ref "JP4") (pin "1") (pinfunction "1_1") (pintype "passive"))
      (node (ref "R51") (pin "2") (pinfunction "2_2") (pintype "passive"))
      (node (ref "U73") (pin "P$7") (pinfunction "CANH_P$7") (pintype "bidirectional"))
    )
    (net (code "9") (name "CANL") (class "Default")
      (node (ref "JP4") (pin "3") (pinfunction "3_3") (pintype "passive"))
      (node (ref "R51") (pin "1") (pinfunction "1_1") (pintype "passive"))
      (node (ref "U73") (pin "P$6") (pinfunction "CANL_P$6") (pintype "bidirectional"))
    )
    (net (code "10") (name "CAN_RX") (class "Default")
      (node (ref "U$2") (pin "P$97") (pinfunction "PB8_P$97") (pintype "bidirectional"))
      (node (ref "U73") (pin "P$4") (pinfunction "R_P$4") (pintype "bidirectional"))
    )
    (net (code "11") (name "CAN_TX") (class "Default")
      (node (ref "U$2") (pin "P$98") (pinfunction "PB9_P$98") (pintype "bidirectional"))
      (node (ref "U73") (pin "P$1") (pinfunction "D_P$1") (pintype "bidirectional"))
    )
    (net (code "12") (name "DM") (class "Default")
      (node (ref "R68") (pin "2") (pinfunction "2_2") (pintype "passive"))
      (node (ref "USB2") (pin "2") (pinfunction "2_2") (pintype "passive"))
    )
    (net (code "13") (name "DP") (class "Default")
      (node (ref "R69") (pin "2") (pinfunction "2_2") (pintype "passive"))
      (node (ref "USB2") (pin "3") (pinfunction "3_3") (pintype "passive"))
    )
    (net (code "14") (name "FAULT") (class "Default")
      (node (ref "U$2") (pin "P$89") (pinfunction "PC12_P$89") (pintype "bidirectional"))
    )
    (net (code "15") (name "GND") (class "Default")
      (node (ref "C10") (pin "1") (pinfunction "1_1") (pintype "passive"))
      (node (ref "C11") (pin "1") (pinfunction "1_1") (pintype "passive"))
      (node (ref "C13") (pin "1") (pinfunction "1_1") (pintype "passive"))
      (node (ref "C16") (pin "1") (pinfunction "1_1") (pintype "passive"))
      (node (ref "C17") (pin "-") (pinfunction "-_-") (pintype "passive"))
      (node (ref "C18") (pin "-") (pinfunction "-_-") (pintype "passive"))
      (node (ref "C19") (pin "2") (pinfunction "2_2") (pintype "passive"))
      (node (ref "C20") (pin "1") (pinfunction "1_1") (pintype "passive"))
      (node (ref "C21") (pin "-") (pinfunction "-_-") (pintype "passive"))
      (node (ref "C22") (pin "1") (pinfunction "1_1") (pintype "passive"))
      (node (ref "C23") (pin "1") (pinfunction "1_1") (pintype "passive"))
      (node (ref "C24") (pin "2") (pinfunction "2_2") (pintype "passive"))
      (node (ref "C25") (pin "2") (pinfunction "2_2") (pintype "passive"))
      (node (ref "C26") (pin "1") (pinfunction "1_1") (pintype "passive"))
      (node (ref "C27") (pin "2") (pinfunction "2_2") (pintype "passive"))
      (node (ref "C28") (pin "2") (pinfunction "2_2") (pintype "passive"))
      (node (ref "C29") (pin "-") (pinfunction "-_-") (pintype "passive"))
      (node (ref "C3") (pin "1") (pinfunction "1_1") (pintype "passive"))
      (node (ref "C30") (pin "-") (pinfunction "-_-") (pintype "passive"))
      (node (ref "C31") (pin "1") (pinfunction "1_1") (pintype "passive"))
      (node (ref "C32") (pin "1") (pinfunction "1_1") (pintype "passive"))
      (node (ref "C33") (pin "1") (pinfunction "1_1") (pintype "passive"))
      (node (ref "C36") (pin "2") (pinfunction "2_2") (pintype "passive"))
      (node (ref "C37") (pin "1") (pinfunction "1_1") (pintype "passive"))
      (node (ref "C38") (pin "2") (pinfunction "2_2") (pintype "passive"))
      (node (ref "C39") (pin "1") (pinfunction "1_1") (pintype "passive"))
      (node (ref "C4") (pin "2") (pinfunction "2_2") (pintype "passive"))
      (node (ref "C40") (pin "1") (pinfunction "1_1") (pintype "passive"))
      (node (ref "C41") (pin "1") (pinfunction "1_1") (pintype "passive"))
      (node (ref "C42") (pin "1") (pinfunction "1_1") (pintype "passive"))
      (node (ref "C43") (pin "1") (pinfunction "1_1") (pintype "passive"))
      (node (ref "C44") (pin "2") (pinfunction "2_2") (pintype "passive"))
      (node (ref "C45") (pin "2") (pinfunction "2_2") (pintype "passive"))
      (node (ref "C49") (pin "2") (pinfunction "2_2") (pintype "passive"))
      (node (ref "C52") (pin "2") (pinfunction "2_2") (pintype "passive"))
      (node (ref "C53") (pin "2") (pinfunction "2_2") (pintype "passive"))
      (node (ref "C56") (pin "2") (pinfunction "2_2") (pintype "passive"))
      (node (ref "C57") (pin "2") (pinfunction "2_2") (pintype "passive"))
      (node (ref "C58") (pin "2") (pinfunction "2_2") (pintype "passive"))
      (node (ref "C59") (pin "2") (pinfunction "2_2") (pintype "passive"))
      (node (ref "C61") (pin "2") (pinfunction "2_2") (pintype "passive"))
      (node (ref "C62") (pin "1") (pinfunction "1_1") (pintype "passive"))
      (node (ref "C63") (pin "-") (pinfunction "-_-") (pintype "passive"))
      (node (ref "C64") (pin "2") (pinfunction "2_2") (pintype "passive"))
      (node (ref "C65") (pin "2") (pinfunction "2_2") (pintype "passive"))
      (node (ref "C66") (pin "1") (pinfunction "1_1") (pintype "passive"))
      (node (ref "C69") (pin "1") (pinfunction "1_1") (pintype "passive"))
      (node (ref "C7") (pin "2") (pinfunction "2_2") (pintype "passive"))
      (node (ref "C77") (pin "2") (pinfunction "2_2") (pintype "passive"))
      (node (ref "C78") (pin "2") (pinfunction "2_2") (pintype "passive"))
      (node (ref "C8") (pin "2") (pinfunction "2_2") (pintype "passive"))
      (node (ref "C9") (pin "2") (pinfunction "2_2") (pintype "passive"))
      (node (ref "D7") (pin "1") (pinfunction "A_1") (pintype "passive"))
      (node (ref "D8") (pin "1") (pinfunction "A_1") (pintype "passive"))
      (node (ref "D9") (pin "1") (pinfunction "A_1") (pintype "passive"))
      (node (ref "JP1") (pin "3") (pinfunction "3_3") (pintype "passive"))
      (node (ref "JP2") (pin "2") (pinfunction "2_2") (pintype "passive"))
      (node (ref "JP3") (pin "1") (pinfunction "1_1") (pintype "passive"))
      (node (ref "JP4") (pin "2") (pinfunction "2_2") (pintype "passive"))
      (node (ref "LD1") (pin "K") (pinfunction "C_K") (pintype "passive"))
      (node (ref "LD3") (pin "K") (pinfunction "C_K") (pintype "passive"))
      (node (ref "LD4") (pin "K") (pinfunction "C_K") (pintype "passive"))
      (node (ref "R19") (pin "P$2") (pinfunction "2_P$2") (pintype "passive"))
      (node (ref "R20") (pin "2") (pinfunction "2_2") (pintype "passive"))
      (node (ref "R21") (pin "1") (pinfunction "1_1") (pintype "passive"))
      (node (ref "R24") (pin "P$2") (pinfunction "2_P$2") (pintype "passive"))
      (node (ref "R26") (pin "P$1") (pinfunction "1_P$1") (pintype "passive"))
      (node (ref "R28") (pin "1") (pinfunction "1_1") (pintype "passive"))
      (node (ref "R3") (pin "P$2") (pinfunction "2_P$2") (pintype "passive"))
      (node (ref "R39") (pin "P$1") (pinfunction "1_P$1") (pintype "passive"))
      (node (ref "R4") (pin "2") (pinfunction "2_2") (pintype "passive"))
      (node (ref "R44") (pin "P$1") (pinfunction "1_P$1") (pintype "passive"))
      (node (ref "R46") (pin "P$1") (pinfunction "1_P$1") (pintype "passive"))
      (node (ref "R57") (pin "1") (pinfunction "1_1") (pintype "passive"))
      (node (ref "R61") (pin "1") (pinfunction "1_1") (pintype "passive"))
      (node (ref "R71") (pin "P$1") (pinfunction "1_P$1") (pintype "passive"))
      (node (ref "R8") (pin "P$2") (pinfunction "2_P$2") (pintype "passive"))
      (node (ref "R84") (pin "2") (pinfunction "2_2") (pintype "passive"))
      (node (ref "R89") (pin "1") (pinfunction "1_1") (pintype "passive"))
      (node (ref "R9") (pin "P$2") (pinfunction "2_P$2") (pintype "passive"))
      (node (ref "R92") (pin "2") (pinfunction "2_2") (pintype "passive"))
      (node (ref "R93") (pin "2") (pinfunction "2_2") (pintype "passive"))
      (node (ref "R94") (pin "2") (pinfunction "2_2") (pintype "passive"))
      (node (ref "R95") (pin "2") (pinfunction "2_2") (pintype "passive"))
      (node (ref "R96") (pin "2") (pinfunction "2_2") (pintype "passive"))
      (node (ref "U$1") (pin "IN-") (pinfunction "IN-_IN-") (pintype "bidirectional"))
      (node (ref "U$1") (pin "OUT-") (pinfunction "OUT-_OUT-") (pintype "bidirectional"))
      (node (ref "U$10") (pin "S") (pinfunction "S_S") (pintype "passive"))
      (node (ref "U$13") (pin "S") (pinfunction "S_S") (pintype "passive"))
      (node (ref "U$14") (pin "S") (pinfunction "S_S") (pintype "passive"))
      (node (ref "U$19") (pin "P$1") (pinfunction "P$1_P$1") (pintype "bidirectional"))
      (node (ref "U$2") (pin "P$12") (pinfunction "VSSA_P$12") (pintype "bidirectional"))
      (node (ref "U$2") (pin "P$27") (pinfunction "VSS1_P$27") (pintype "bidirectional"))
      (node (ref "U$2") (pin "P$96") (pinfunction "BOOT0_P$96") (pintype "bidirectional"))
      (node (ref "U$20") (pin "2") (pinfunction "GND_2") (pintype "bidirectional"))
      (node (ref "U$21") (pin "2") (pinfunction "GND_2") (pintype "bidirectional"))
      (node (ref "U$5") (pin "S") (pinfunction "S_S") (pintype "passive"))
      (node (ref "U$6") (pin "S") (pinfunction "S_S") (pintype "passive"))
      (node (ref "U$9") (pin "S") (pinfunction "S_S") (pintype "passive"))
      (node (ref "U1") (pin "15") (pinfunction "VSS_15") (pintype "input"))
      (node (ref "U1") (pin "2") (pinfunction "COM_2") (pintype "output"))
      (node (ref "U11") (pin "1") (pinfunction "ADJ_1") (pintype "input"))
      (node (ref "U2") (pin "15") (pinfunction "VSS_15") (pintype "input"))
      (node (ref "U2") (pin "2") (pinfunction "COM_2") (pintype "output"))
      (node (ref "U3") (pin "15") (pinfunction "VSS_15") (pintype "input"))
      (node (ref "U3") (pin "2") (pinfunction "COM_2") (pintype "output"))
      (node (ref "U4") (pin "4") (pinfunction "GND1_4") (pintype "bidirectional"))
      (node (ref "U4") (pin "5") (pinfunction "GND2_5") (pintype "bidirectional"))
      (node (ref "U5") (pin "4") (pinfunction "GND1_4") (pintype "bidirectional"))
      (node (ref "U5") (pin "5") (pinfunction "GND2_5") (pintype "bidirectional"))
      (node (ref "U6") (pin "4") (pinfunction "GND1_4") (pintype "bidirectional"))
      (node (ref "U6") (pin "5") (pinfunction "GND2_5") (pintype "bidirectional"))
      (node (ref "U73") (pin "P$2") (pinfunction "GND_P$2") (pintype "bidirectional"))
      (node (ref "U9") (pin "1") (pinfunction "ADJ_1") (pintype "input"))
      (node (ref "USB2") (pin "5") (pinfunction "5_5") (pintype "passive"))
      (node (ref "X2") (pin "2") (pinfunction "2_2") (pintype "bidirectional"))
      (node (ref "X2") (pin "4") (pinfunction "4_4") (pintype "bidirectional"))
      (node (ref "Z3") (pin "A") (pinfunction "A_A") (pintype "passive"))
      (node (ref "Z4") (pin "A") (pinfunction "A_A") (pintype "passive"))
      (node (ref "Z6") (pin "A") (pinfunction "A_A") (pintype "passive"))
    )
    (net (code "16") (name "H1") (class "Default")
      (node (ref "R4") (pin "1") (pinfunction "1_1") (pintype "passive"))
      (node (ref "R83") (pin "1") (pinfunction "1_1") (pintype "passive"))
      (node (ref "U$2") (pin "P$70") (pinfunction "PA10_P$70") (pintype "bidirectional"))
    )
    (net (code "17") (name "H1_VS2") (class "Default")
      (node (ref "C12") (pin "-") (pinfunction "-_-") (pintype "passive"))
      (node (ref "C14") (pin "2") (pinfunction "2_2") (pintype "passive"))
      (node (ref "C15") (pin "2") (pinfunction "2_2") (pintype "passive"))
      (node (ref "C75") (pin "1") (pinfunction "1_1") (pintype "passive"))
      (node (ref "R14") (pin "P$1") (pinfunction "1_P$1") (pintype "passive"))
      (node (ref "R16") (pin "P$1") (pinfunction "1_P$1") (pintype "passive"))
      (node (ref "R7") (pin "P$2") (pinfunction "2_P$2") (pintype "passive"))
      (node (ref "U$15") (pin "P$1") (pinfunction "P$1_P$1") (pintype "bidirectional"))
      (node (ref "U$3") (pin "S") (pinfunction "S_S") (pintype "passive"))
      (node (ref "U$4") (pin "S") (pinfunction "S_S") (pintype "passive"))
      (node (ref "U$5") (pin "D") (pinfunction "D_D") (pintype "passive"))
      (node (ref "U$6") (pin "D") (pinfunction "D_D") (pintype "passive"))
      (node (ref "U1") (pin "6") (pinfunction "VS_6") (pintype "output"))
      (node (ref "Z2") (pin "A") (pinfunction "A_A") (pintype "passive"))
    )
    (net (code "18") (name "H2") (class "Default")
      (node (ref "R100") (pin "1") (pinfunction "1_1") (pintype "passive"))
      (node (ref "R93") (pin "1") (pinfunction "1_1") (pintype "passive"))
      (node (ref "U$2") (pin "P$69") (pinfunction "PA9_P$69") (pintype "bidirectional"))
    )
    (net (code "19") (name "H2_VS4") (class "Default")
      (node (ref "C1") (pin "-") (pinfunction "-_-") (pintype "passive"))
      (node (ref "C2") (pin "1") (pinfunction "1_1") (pintype "passive"))
      (node (ref "C34") (pin "2") (pinfunction "2_2") (pintype "passive"))
      (node (ref "C35") (pin "2") (pinfunction "2_2") (pintype "passive"))
      (node (ref "R34") (pin "P$1") (pinfunction "1_P$1") (pintype "passive"))
      (node (ref "R36") (pin "P$1") (pinfunction "1_P$1") (pintype "passive"))
      (node (ref "R6") (pin "P$2") (pinfunction "2_P$2") (pintype "passive"))
      (node (ref "U$10") (pin "D") (pinfunction "D_D") (pintype "passive"))
      (node (ref "U$16") (pin "P$1") (pinfunction "P$1_P$1") (pintype "bidirectional"))
      (node (ref "U$7") (pin "S") (pinfunction "S_S") (pintype "passive"))
      (node (ref "U$8") (pin "S") (pinfunction "S_S") (pintype "passive"))
      (node (ref "U$9") (pin "D") (pinfunction "D_D") (pintype "passive"))
      (node (ref "U2") (pin "6") (pinfunction "VS_6") (pintype "output"))
      (node (ref "Z1") (pin "A") (pinfunction "A_A") (pintype "passive"))
    )
    (net (code "20") (name "H3") (class "Default")
      (node (ref "R102") (pin "1") (pinfunction "1_1") (pintype "passive"))
      (node (ref "R95") (pin "1") (pinfunction "1_1") (pintype "passive"))
      (node (ref "U$2") (pin "P$68") (pinfunction "PA8_P$68") (pintype "bidirectional"))
    )
    (net (code "21") (name "H3_VS4") (class "Default")
      (node (ref "C5") (pin "-") (pinfunction "-_-") (pintype "passive"))
      (node (ref "C54") (pin "2") (pinfunction "2_2") (pintype "passive"))
      (node (ref "C55") (pin "2") (pinfunction "2_2") (pintype "passive"))
      (node (ref "C6") (pin "1") (pinfunction "1_1") (pintype "passive"))
      (node (ref "R5") (pin "P$2") (pinfunction "2_P$2") (pintype "passive"))
      (node (ref "R54") (pin "P$1") (pinfunction "1_P$1") (pintype "passive"))
      (node (ref "R56") (pin "P$1") (pinfunction "1_P$1") (pintype "passive"))
      (node (ref "U$11") (pin "S") (pinfunction "S_S") (pintype "passive"))
      (node (ref "U$12") (pin "S") (pinfunction "S_S") (pintype "passive"))
      (node (ref "U$13") (pin "D") (pinfunction "D_D") (pintype "passive"))
      (node (ref "U$14") (pin "D") (pinfunction "D_D") (pintype "passive"))
      (node (ref "U$17") (pin "P$1") (pinfunction "P$1_P$1") (pintype "bidirectional"))
      (node (ref "U3") (pin "6") (pinfunction "VS_6") (pintype "output"))
      (node (ref "Z5") (pin "A") (pinfunction "A_A") (pintype "passive"))
    )
    (net (code "22") (name "HALL1_IN") (class "Default")
      (node (ref "JP2") (pin "5") (pinfunction "5_5") (pintype "passive"))
      (node (ref "R38") (pin "2") (pinfunction "2_2") (pintype "passive"))
      (node (ref "R40") (pin "1") (pinfunction "1_1") (pintype "passive"))
    )
    (net (code "23") (name "HALL1_OUT") (class "Default")
      (node (ref "R29") (pin "1") (pinfunction "1_1") (pintype "passive"))
      (node (ref "U$2") (pin "P$94") (pinfunction "PB6_P$94") (pintype "bidirectional"))
    )
    (net (code "24") (name "HALL2_IN") (class "Default")
      (node (ref "JP2") (pin "4") (pinfunction "4_4") (pintype "passive"))
      (node (ref "R41") (pin "2") (pinfunction "2_2") (pintype "passive"))
      (node (ref "R47") (pin "1") (pinfunction "1_1") (pintype "passive"))
    )
    (net (code "25") (name "HALL2_OUT") (class "Default")
      (node (ref "R91") (pin "1") (pinfunction "1_1") (pintype "passive"))
      (node (ref "U$2") (pin "P$95") (pinfunction "PB7_P$95") (pintype "bidirectional"))
    )
    (net (code "26") (name "HALL3_IN") (class "Default")
      (node (ref "JP2") (pin "3") (pinfunction "3_3") (pintype "passive"))
      (node (ref "R48") (pin "2") (pinfunction "2_2") (pintype "passive"))
      (node (ref "R49") (pin "1") (pinfunction "1_1") (pintype "passive"))
    )
    (net (code "27") (name "HALL3_OUT") (class "Default")
      (node (ref "R37") (pin "1") (pinfunction "1_1") (pintype "passive"))
      (node (ref "U$2") (pin "P$88") (pinfunction "PC11_P$88") (pintype "bidirectional"))
    )
    (net (code "28") (name "IN1") (class "Default")
      (node (ref "R60") (pin "2") (pinfunction "2_2") (pintype "passive"))
      (node (ref "R67") (pin "1") (pinfunction "1_1") (pintype "passive"))
    )
    (net (code "29") (name "IN2") (class "Default")
      (node (ref "R64") (pin "2") (pinfunction "2_2") (pintype "passive"))
      (node (ref "R66") (pin "1") (pinfunction "1_1") (pintype "passive"))
    )
    (net (code "30") (name "IN3") (class "Default")
      (node (ref "R58") (pin "2") (pinfunction "2_2") (pintype "passive"))
      (node (ref "R59") (pin "1") (pinfunction "1_1") (pintype "passive"))
    )
    (net (code "31") (name "IN4") (class "Default")
      (node (ref "U$2") (pin "P$38") (pinfunction "PB10_P$38") (pintype "bidirectional"))
    )
    (net (code "32") (name "KONTAK") (class "Default")
      (node (ref "D10") (pin "A") (pinfunction "A_A") (pintype "passive"))
      (node (ref "U$22") (pin "P$1") (pinfunction "P$1_P$1") (pintype "bidirectional"))
    )
    (net (code "33") (name "KONTAKTOR") (class "Default")
      (node (ref "U$2") (pin "P$92") (pinfunction "PB4_P$92") (pintype "bidirectional"))
    )
    (net (code "34") (name "L1") (class "Default")
      (node (ref "R82") (pin "1") (pinfunction "1_1") (pintype "passive"))
      (node (ref "R92") (pin "1") (pinfunction "1_1") (pintype "passive"))
      (node (ref "U$2") (pin "P$63") (pinfunction "PB15_P$63") (pintype "bidirectional"))
    )
    (net (code "35") (name "L2") (class "Default")
      (node (ref "R94") (pin "1") (pinfunction "1_1") (pintype "passive"))
      (node (ref "R99") (pin "1") (pinfunction "1_1") (pintype "passive"))
      (node (ref "U$2") (pin "P$62") (pinfunction "PB14_P$62") (pintype "bidirectional"))
    )
    (net (code "36") (name "L3") (class "Default")
      (node (ref "R101") (pin "1") (pinfunction "1_1") (pintype "passive"))
      (node (ref "R96") (pin "1") (pinfunction "1_1") (pintype "passive"))
      (node (ref "U$2") (pin "P$61") (pinfunction "PB13_P$61") (pintype "bidirectional"))
    )
    (net (code "37") (name "NOT_FITTED") (class "Default")
      (node (ref "U$2") (pin "P$17") (pinfunction "VSS2_P$17") (pintype "bidirectional"))
    )
    (net (code "38") (name "Net-(D7-AC)") (class "Default")
      (node (ref "C52") (pin "1") (pinfunction "1_1") (pintype "passive"))
      (node (ref "D7") (pin "3") (pinfunction "AC_3") (pintype "passive"))
      (node (ref "R29") (pin "2") (pinfunction "2_2") (pintype "passive"))
      (node (ref "R38") (pin "1") (pinfunction "1_1") (pintype "passive"))
    )
    (net (code "39") (name "Net-(D8-AC)") (class "Default")
      (node (ref "C53") (pin "1") (pinfunction "1_1") (pintype "passive"))
      (node (ref "D8") (pin "3") (pinfunction "AC_3") (pintype "passive"))
      (node (ref "R41") (pin "1") (pinfunction "1_1") (pintype "passive"))
      (node (ref "R91") (pin "2") (pinfunction "2_2") (pintype "passive"))
    )
    (net (code "40") (name "Net-(D9-AC)") (class "Default")
      (node (ref "C57") (pin "1") (pinfunction "1_1") (pintype "passive"))
      (node (ref "D9") (pin "3") (pinfunction "AC_3") (pintype "passive"))
      (node (ref "R37") (pin "2") (pinfunction "2_2") (pintype "passive"))
      (node (ref "R48") (pin "1") (pinfunction "1_1") (pintype "passive"))
    )
    (net (code "41") (name "Net-(D10-PadC)") (class "Default")
      (node (ref "D10") (pin "C") (pinfunction "C_C") (pintype "passive"))
      (node (ref "U$1") (pin "IN+") (pinfunction "IN+_IN+") (pintype "bidirectional"))
    )
    (net (code "42") (name "Net-(LD1-PadA)") (class "Default")
      (node (ref "LD1") (pin "A") (pinfunction "A_A") (pintype "passive"))
      (node (ref "R50") (pin "1") (pinfunction "1_1") (pintype "passive"))
    )
    (net (code "43") (name "Net-(LD3-PadA)") (class "Default")
      (node (ref "LD3") (pin "A") (pinfunction "A_A") (pintype "passive"))
      (node (ref "R18") (pin "1") (pinfunction "1_1") (pintype "passive"))
    )
    (net (code "44") (name "Net-(LD4-PadA)") (class "Default")
      (node (ref "LD4") (pin "A") (pinfunction "A_A") (pintype "passive"))
      (node (ref "R27") (pin "1") (pinfunction "1_1") (pintype "passive"))
    )
    (net (code "45") (name "Net-(R1-2)") (class "Default")
      (node (ref "R1") (pin "P$2") (pinfunction "2_P$2") (pintype "passive"))
      (node (ref "R85") (pin "P$2") (pinfunction "2_P$2") (pintype "passive"))
    )
    (net (code "46") (name "Net-(R3-1)") (class "Default")
      (node (ref "R3") (pin "P$1") (pinfunction "1_P$1") (pintype "passive"))
      (node (ref "R85") (pin "P$1") (pinfunction "1_P$1") (pintype "passive"))
      (node (ref "R90") (pin "P$2") (pinfunction "2_P$2") (pintype "passive"))
    )
    (net (code "47") (name "Net-(R5-1)") (class "Default")
      (node (ref "R5") (pin "P$1") (pinfunction "1_P$1") (pintype "passive"))
      (node (ref "R88") (pin "P$2") (pinfunction "2_P$2") (pintype "passive"))
    )
    (net (code "48") (name "Net-(R6-1)") (class "Default")
      (node (ref "R6") (pin "P$1") (pinfunction "1_P$1") (pintype "passive"))
      (node (ref "R87") (pin "P$2") (pinfunction "2_P$2") (pintype "passive"))
    )
    (net (code "49") (name "Net-(R7-1)") (class "Default")
      (node (ref "R7") (pin "P$1") (pinfunction "1_P$1") (pintype "passive"))
      (node (ref "R86") (pin "P$2") (pinfunction "2_P$2") (pintype "passive"))
    )
    (net (code "50") (name "Net-(R12-1)") (class "Default")
      (node (ref "R12") (pin "P$1") (pinfunction "1_P$1") (pintype "passive"))
      (node (ref "R13") (pin "P$2") (pinfunction "2_P$2") (pintype "passive"))
      (node (ref "R15") (pin "P$2") (pinfunction "2_P$2") (pintype "passive"))
      (node (ref "Z2") (pin "C") (pinfunction "C_C") (pintype "passive"))
    )
    (net (code "51") (name "Net-(R12-2)") (class "Default")
      (node (ref "R12") (pin "P$2") (pinfunction "2_P$2") (pintype "passive"))
      (node (ref "U1") (pin "8") (pinfunction "HO_8") (pintype "bidirectional"))
    )
    (net (code "52") (name "Net-(R13-1)") (class "Default")
      (node (ref "C14") (pin "1") (pinfunction "1_1") (pintype "passive"))
      (node (ref "R13") (pin "P$1") (pinfunction "1_P$1") (pintype "passive"))
      (node (ref "R14") (pin "P$2") (pinfunction "2_P$2") (pintype "passive"))
      (node (ref "U$3") (pin "G") (pinfunction "G_G") (pintype "passive"))
    )
    (net (code "53") (name "Net-(R15-1)") (class "Default")
      (node (ref "C15") (pin "1") (pinfunction "1_1") (pintype "passive"))
      (node (ref "R15") (pin "P$1") (pinfunction "1_P$1") (pintype "passive"))
      (node (ref "R16") (pin "P$2") (pinfunction "2_P$2") (pintype "passive"))
      (node (ref "U$4") (pin "G") (pinfunction "G_G") (pintype "passive"))
    )
    (net (code "54") (name "Net-(R22-1)") (class "Default")
      (node (ref "R22") (pin "P$1") (pinfunction "1_P$1") (pintype "passive"))
      (node (ref "R23") (pin "P$2") (pinfunction "2_P$2") (pintype "passive"))
      (node (ref "R25") (pin "P$2") (pinfunction "2_P$2") (pintype "passive"))
      (node (ref "Z3") (pin "C") (pinfunction "C_C") (pintype "passive"))
    )
    (net (code "55") (name "Net-(R22-2)") (class "Default")
      (node (ref "R22") (pin "P$2") (pinfunction "2_P$2") (pintype "passive"))
      (node (ref "U1") (pin "1") (pinfunction "LO_1") (pintype "input"))
    )
    (net (code "56") (name "Net-(R23-1)") (class "Default")
      (node (ref "C24") (pin "1") (pinfunction "1_1") (pintype "passive"))
      (node (ref "R23") (pin "P$1") (pinfunction "1_P$1") (pintype "passive"))
      (node (ref "R24") (pin "P$1") (pinfunction "1_P$1") (pintype "passive"))
      (node (ref "U$5") (pin "G") (pinfunction "G_G") (pintype "passive"))
    )
    (net (code "57") (name "Net-(R25-1)") (class "Default")
      (node (ref "C25") (pin "1") (pinfunction "1_1") (pintype "passive"))
      (node (ref "R25") (pin "P$1") (pinfunction "1_P$1") (pintype "passive"))
      (node (ref "R26") (pin "P$2") (pinfunction "2_P$2") (pintype "passive"))
      (node (ref "U$6") (pin "G") (pinfunction "G_G") (pintype "passive"))
    )
    (net (code "58") (name "Net-(R32-1)") (class "Default")
      (node (ref "R32") (pin "P$1") (pinfunction "1_P$1") (pintype "passive"))
      (node (ref "U2") (pin "8") (pinfunction "HO_8") (pintype "bidirectional"))
    )
    (net (code "59") (name "Net-(R32-2)") (class "Default")
      (node (ref "R32") (pin "P$2") (pinfunction "2_P$2") (pintype "passive"))
      (node (ref "R33") (pin "P$2") (pinfunction "2_P$2") (pintype "passive"))
      (node (ref "R35") (pin "P$2") (pinfunction "2_P$2") (pintype "passive"))
      (node (ref "Z1") (pin "C") (pinfunction "C_C") (pintype "passive"))
    )
    (net (code "60") (name "Net-(R33-1)") (class "Default")
      (node (ref "C34") (pin "1") (pinfunction "1_1") (pintype "passive"))
      (node (ref "R33") (pin "P$1") (pinfunction "1_P$1") (pintype "passive"))
      (node (ref "R34") (pin "P$2") (pinfunction "2_P$2") (pintype "passive"))
      (node (ref "U$7") (pin "G") (pinfunction "G_G") (pintype "passive"))
    )
    (net (code "61") (name "Net-(R35-1)") (class "Default")
      (node (ref "C35") (pin "1") (pinfunction "1_1") (pintype "passive"))
      (node (ref "R35") (pin "P$1") (pinfunction "1_P$1") (pintype "passive"))
      (node (ref "R36") (pin "P$2") (pinfunction "2_P$2") (pintype "passive"))
      (node (ref "U$8") (pin "G") (pinfunction "G_G") (pintype "passive"))
    )
    (net (code "62") (name "Net-(R39-2)") (class "Default")
      (node (ref "C65") (pin "1") (pinfunction "1_1") (pintype "passive"))
      (node (ref "R39") (pin "P$2") (pinfunction "2_P$2") (pintype "passive"))
      (node (ref "R65") (pin "P$1") (pinfunction "1_P$1") (pintype "passive"))
      (node (ref "U$14") (pin "G") (pinfunction "G_G") (pintype "passive"))
    )
    (net (code "63") (name "Net-(R42-1)") (class "Default")
      (node (ref "R42") (pin "P$1") (pinfunction "1_P$1") (pintype "passive"))
      (node (ref "R43") (pin "P$2") (pinfunction "2_P$2") (pintype "passive"))
      (node (ref "R45") (pin "P$2") (pinfunction "2_P$2") (pintype "passive"))
      (node (ref "Z4") (pin "C") (pinfunction "C_C") (pintype "passive"))
    )
    (net (code "64") (name "Net-(R42-2)") (class "Default")
      (node (ref "R42") (pin "P$2") (pinfunction "2_P$2") (pintype "passive"))
      (node (ref "U2") (pin "1") (pinfunction "LO_1") (pintype "input"))
    )
    (net (code "65") (name "Net-(R43-1)") (class "Default")
      (node (ref "C44") (pin "1") (pinfunction "1_1") (pintype "passive"))
      (node (ref "R43") (pin "P$1") (pinfunction "1_P$1") (pintype "passive"))
      (node (ref "R44") (pin "P$2") (pinfunction "2_P$2") (pintype "passive"))
      (node (ref "U$10") (pin "G") (pinfunction "G_G") (pintype "passive"))
    )
    (net (code "66") (name "Net-(R45-1)") (class "Default")
      (node (ref "C45") (pin "1") (pinfunction "1_1") (pintype "passive"))
      (node (ref "R45") (pin "P$1") (pinfunction "1_P$1") (pintype "passive"))
      (node (ref "R46") (pin "P$2") (pinfunction "2_P$2") (pintype "passive"))
      (node (ref "U$9") (pin "G") (pinfunction "G_G") (pintype "passive"))
    )
    (net (code "67") (name "Net-(R52-1)") (class "Default")
      (node (ref "R52") (pin "P$1") (pinfunction "1_P$1") (pintype "passive"))
      (node (ref "R53") (pin "P$2") (pinfunction "2_P$2") (pintype "passive"))
      (node (ref "R55") (pin "P$2") (pinfunction "2_P$2") (pintype "passive"))
      (node (ref "Z5") (pin "C") (pinfunction "C_C") (pintype "passive"))
    )
    (net (code "68") (name "Net-(R52-2)") (class "Default")
      (node (ref "R52") (pin "P$2") (pinfunction "2_P$2") (pintype "passive"))
      (node (ref "U3") (pin "8") (pinfunction "HO_8") (pintype "bidirectional"))
    )
    (net (code "69") (name "Net-(R53-1)") (class "Default")
      (node (ref "C54") (pin "1") (pinfunction "1_1") (pintype "passive"))
      (node (ref "R53") (pin "P$1") (pinfunction "1_P$1") (pintype "passive"))
      (node (ref "R54") (pin "P$2") (pinfunction "2_P$2") (pintype "passive"))
      (node (ref "U$11") (pin "G") (pinfunction "G_G") (pintype "passive"))
    )
    (net (code "70") (name "Net-(R55-1)") (class "Default")
      (node (ref "C55") (pin "1") (pinfunction "1_1") (pintype "passive"))
      (node (ref "R55") (pin "P$1") (pinfunction "1_P$1") (pintype "passive"))
      (node (ref "R56") (pin "P$2") (pinfunction "2_P$2") (pintype "passive"))
      (node (ref "U$12") (pin "G") (pinfunction "G_G") (pintype "passive"))
    )
    (net (code "71") (name "Net-(R62-1)") (class "Default")
      (node (ref "R62") (pin "P$1") (pinfunction "1_P$1") (pintype "passive"))
      (node (ref "R63") (pin "P$2") (pinfunction "2_P$2") (pintype "passive"))
      (node (ref "R65") (pin "P$2") (pinfunction "2_P$2") (pintype "passive"))
      (node (ref "Z6") (pin "C") (pinfunction "C_C") (pintype "passive"))
    )
    (net (code "72") (name "Net-(R62-2)") (class "Default")
      (node (ref "R62") (pin "P$2") (pinfunction "2_P$2") (pintype "passive"))
      (node (ref "U3") (pin "1") (pinfunction "LO_1") (pintype "input"))
    )
    (net (code "73") (name "Net-(R63-1)") (class "Default")
      (node (ref "C64") (pin "1") (pinfunction "1_1") (pintype "passive"))
      (node (ref "R63") (pin "P$1") (pinfunction "1_P$1") (pintype "passive"))
      (node (ref "R71") (pin "P$2") (pinfunction "2_P$2") (pintype "passive"))
      (node (ref "U$13") (pin "G") (pinfunction "G_G") (pintype "passive"))
    )
    (net (code "74") (name "Net-(R103-2)") (class "Default")
      (node (ref "R103") (pin "P$2") (pinfunction "2_P$2") (pintype "passive"))
      (node (ref "R8") (pin "P$1") (pinfunction "1_P$1") (pintype "passive"))
      (node (ref "R86") (pin "P$1") (pinfunction "1_P$1") (pintype "passive"))
    )
    (net (code "75") (name "Net-(R104-2)") (class "Default")
      (node (ref "R104") (pin "P$2") (pinfunction "2_P$2") (pintype "passive"))
      (node (ref "R87") (pin "P$1") (pinfunction "1_P$1") (pintype "passive"))
      (node (ref "R9") (pin "P$1") (pinfunction "1_P$1") (pintype "passive"))
    )
    (net (code "76") (name "Net-(R105-2)") (class "Default")
      (node (ref "R105") (pin "P$2") (pinfunction "2_P$2") (pintype "passive"))
      (node (ref "R19") (pin "P$1") (pinfunction "1_P$1") (pintype "passive"))
      (node (ref "R88") (pin "P$1") (pinfunction "1_P$1") (pintype "passive"))
    )
    (net (code "77") (name "Net-(U$2-NRST)") (class "Default")
      (node (ref "C37") (pin "2") (pinfunction "2_2") (pintype "passive"))
      (node (ref "U$2") (pin "P$7") (pinfunction "NRST_P$7") (pintype "bidirectional"))
    )
    (net (code "78") (name "Net-(U$2-PA11)") (class "Default")
      (node (ref "R68") (pin "1") (pinfunction "1_1") (pintype "passive"))
      (node (ref "U$2") (pin "P$71") (pinfunction "PA11_P$71") (pintype "bidirectional"))
    )
    (net (code "79") (name "Net-(U$2-PA12)") (class "Default")
      (node (ref "R69") (pin "1") (pinfunction "1_1") (pintype "passive"))
      (node (ref "U$2") (pin "P$72") (pinfunction "PA12_P$72") (pintype "bidirectional"))
    )
    (net (code "80") (name "Net-(U$2-PA13)") (class "Default")
      (node (ref "JP1") (pin "4") (pinfunction "4_4") (pintype "passive"))
      (node (ref "U$2") (pin "P$73") (pinfunction "PA13_P$73") (pintype "bidirectional"))
    )
    (net (code "81") (name "Net-(U$2-PA14)") (class "Default")
      (node (ref "JP1") (pin "2") (pinfunction "2_2") (pintype "passive"))
      (node (ref "U$2") (pin "P$85") (pinfunction "PA14_P$85") (pintype "bidirectional"))
    )
    (net (code "82") (name "Net-(U$2-PB11)") (class "Default")
      (node (ref "R59") (pin "2") (pinfunction "2_2") (pintype "passive"))
      (node (ref "U$2") (pin "P$39") (pinfunction "PB11_P$39") (pintype "bidirectional"))
    )
    (net (code "83") (name "Net-(U$2-PC4)") (class "Default")
      (node (ref "R27") (pin "2") (pinfunction "2_2") (pintype "passive"))
      (node (ref "U$2") (pin "P$33") (pinfunction "PC4_P$33") (pintype "bidirectional"))
    )
    (net (code "84") (name "Net-(U$2-PC5)") (class "Default")
      (node (ref "R50") (pin "2") (pinfunction "2_2") (pintype "passive"))
      (node (ref "U$2") (pin "P$34") (pinfunction "PC5_P$34") (pintype "bidirectional"))
    )
    (net (code "85") (name "Net-(U$2-PC6)") (class "Default")
      (node (ref "R67") (pin "2") (pinfunction "2_2") (pintype "passive"))
      (node (ref "U$2") (pin "P$64") (pinfunction "PC6_P$64") (pintype "bidirectional"))
    )
    (net (code "86") (name "Net-(U$2-PC7)") (class "Default")
      (node (ref "R66") (pin "2") (pinfunction "2_2") (pintype "passive"))
      (node (ref "U$2") (pin "P$65") (pinfunction "PC7_P$65") (pintype "bidirectional"))
    )
    (net (code "87") (name "Net-(U$2-PH0_OSC_IN)") (class "Default")
      (node (ref "C23") (pin "2") (pinfunction "2_2") (pintype "passive"))
      (node (ref "U$2") (pin "P$5") (pinfunction "PH0_OSC_IN_P$5") (pintype "bidirectional"))
      (node (ref "X2") (pin "3") (pinfunction "3_3") (pintype "bidirectional"))
    )
    (net (code "88") (name "Net-(U$2-PH1_OSC_OUT)") (class "Default")
      (node (ref "C56") (pin "1") (pinfunction "1_1") (pintype "passive"))
      (node (ref "U$2") (pin "P$6") (pinfunction "PH1_OSC_OUT_P$6") (pintype "bidirectional"))
      (node (ref "X2") (pin "1") (pinfunction "1_1") (pintype "bidirectional"))
    )
    (net (code "89") (name "Net-(U$2-VCAP1)") (class "Default")
      (node (ref "C26") (pin "2") (pinfunction "2_2") (pintype "passive"))
      (node (ref "U$2") (pin "P$40") (pinfunction "VCAP1_P$40") (pintype "bidirectional"))
    )
    (net (code "90") (name "Net-(U$2-VCAP2)") (class "Default")
      (node (ref "C13") (pin "2") (pinfunction "2_2") (pintype "passive"))
      (node (ref "U$2") (pin "P$74") (pinfunction "VCAP2_P$74") (pintype "bidirectional"))
    )
    (net (code "91") (name "Net-(U1-HIN)") (class "Default")
      (node (ref "R10") (pin "2") (pinfunction "2_2") (pintype "passive"))
      (node (ref "U1") (pin "12") (pinfunction "HIN_12") (pintype "input"))
    )
    (net (code "92") (name "Net-(U1-LIN)") (class "Default")
      (node (ref "R11") (pin "2") (pinfunction "2_2") (pintype "passive"))
      (node (ref "U1") (pin "14") (pinfunction "LIN_14") (pintype "output"))
    )
    (net (code "93") (name "Net-(U1-VB)") (class "Default")
      (node (ref "C12") (pin "+") (pinfunction "+_+") (pintype "passive"))
      (node (ref "C75") (pin "2") (pinfunction "2_2") (pintype "passive"))
      (node (ref "D1") (pin "C") (pinfunction "C_C") (pintype "passive"))
      (node (ref "U1") (pin "7") (pinfunction "VB_7") (pintype "input"))
    )
    (net (code "94") (name "Net-(U2-HIN)") (class "Default")
      (node (ref "R97") (pin "2") (pinfunction "2_2") (pintype "passive"))
      (node (ref "U2") (pin "12") (pinfunction "HIN_12") (pintype "input"))
    )
    (net (code "95") (name "Net-(U2-LIN)") (class "Default")
      (node (ref "R98") (pin "2") (pinfunction "2_2") (pintype "passive"))
      (node (ref "U2") (pin "14") (pinfunction "LIN_14") (pintype "output"))
    )
    (net (code "96") (name "Net-(U2-VB)") (class "Default")
      (node (ref "C1") (pin "+") (pinfunction "+_+") (pintype "passive"))
      (node (ref "C2") (pin "2") (pinfunction "2_2") (pintype "passive"))
      (node (ref "D2") (pin "C") (pinfunction "C_C") (pintype "passive"))
      (node (ref "U2") (pin "7") (pinfunction "VB_7") (pintype "input"))
    )
    (net (code "97") (name "Net-(U3-HIN)") (class "Default")
      (node (ref "R30") (pin "2") (pinfunction "2_2") (pintype "passive"))
      (node (ref "U3") (pin "12") (pinfunction "HIN_12") (pintype "input"))
    )
    (net (code "98") (name "Net-(U3-LIN)") (class "Default")
      (node (ref "R31") (pin "2") (pinfunction "2_2") (pintype "passive"))
      (node (ref "U3") (pin "14") (pinfunction "LIN_14") (pintype "output"))
    )
    (net (code "99") (name "Net-(U3-VB)") (class "Default")
      (node (ref "C5") (pin "+") (pinfunction "+_+") (pintype "passive"))
      (node (ref "C6") (pin "2") (pinfunction "2_2") (pintype "passive"))
      (node (ref "D3") (pin "C") (pinfunction "C_C") (pintype "passive"))
      (node (ref "U3") (pin "7") (pinfunction "VB_7") (pintype "input"))
    )
    (net (code "100") (name "Net-(U4-VIA)") (class "Default")
      (node (ref "R83") (pin "2") (pinfunction "2_2") (pintype "passive"))
      (node (ref "U4") (pin "2") (pinfunction "VIA_2") (pintype "bidirectional"))
    )
    (net (code "101") (name "Net-(U4-VIB)") (class "Default")
      (node (ref "R82") (pin "2") (pinfunction "2_2") (pintype "passive"))
      (node (ref "U4") (pin "3") (pinfunction "VIB_3") (pintype "bidirectional"))
    )
    (net (code "102") (name "Net-(U4-VOA)") (class "Default")
      (node (ref "R10") (pin "1") (pinfunction "1_1") (pintype "passive"))
      (node (ref "U4") (pin "7") (pinfunction "VOA_7") (pintype "bidirectional"))
    )
    (net (code "103") (name "Net-(U4-VOB)") (class "Default")
      (node (ref "R11") (pin "1") (pinfunction "1_1") (pintype "passive"))
      (node (ref "U4") (pin "6") (pinfunction "VOB_6") (pintype "bidirectional"))
    )
    (net (code "104") (name "Net-(U5-VIA)") (class "Default")
      (node (ref "R100") (pin "2") (pinfunction "2_2") (pintype "passive"))
      (node (ref "U5") (pin "2") (pinfunction "VIA_2") (pintype "bidirectional"))
    )
    (net (code "105") (name "Net-(U5-VIB)") (class "Default")
      (node (ref "R99") (pin "2") (pinfunction "2_2") (pintype "passive"))
      (node (ref "U5") (pin "3") (pinfunction "VIB_3") (pintype "bidirectional"))
    )
    (net (code "106") (name "Net-(U5-VOA)") (class "Default")
      (node (ref "R97") (pin "1") (pinfunction "1_1") (pintype "passive"))
      (node (ref "U5") (pin "7") (pinfunction "VOA_7") (pintype "bidirectional"))
    )
    (net (code "107") (name "Net-(U5-VOB)") (class "Default")
      (node (ref "R98") (pin "1") (pinfunction "1_1") (pintype "passive"))
      (node (ref "U5") (pin "6") (pinfunction "VOB_6") (pintype "bidirectional"))
    )
    (net (code "108") (name "Net-(U6-VIA)") (class "Default")
      (node (ref "R102") (pin "2") (pinfunction "2_2") (pintype "passive"))
      (node (ref "U6") (pin "2") (pinfunction "VIA_2") (pintype "bidirectional"))
    )
    (net (code "109") (name "Net-(U6-VIB)") (class "Default")
      (node (ref "R101") (pin "2") (pinfunction "2_2") (pintype "passive"))
      (node (ref "U6") (pin "3") (pinfunction "VIB_3") (pintype "bidirectional"))
    )
    (net (code "110") (name "Net-(U6-VOA)") (class "Default")
      (node (ref "R30") (pin "1") (pinfunction "1_1") (pintype "passive"))
      (node (ref "U6") (pin "7") (pinfunction "VOA_7") (pintype "bidirectional"))
    )
    (net (code "111") (name "Net-(U6-VOB)") (class "Default")
      (node (ref "R31") (pin "1") (pinfunction "1_1") (pintype "passive"))
      (node (ref "U6") (pin "6") (pinfunction "VOB_6") (pintype "bidirectional"))
    )
    (net (code "112") (name "Net-(U73-RS)") (class "Default")
      (node (ref "R57") (pin "2") (pinfunction "2_2") (pintype "passive"))
      (node (ref "U73") (pin "P$8") (pinfunction "RS_P$8") (pintype "bidirectional"))
    )
    (net (code "113") (name "PRECHARGE") (class "Default")
      (node (ref "U$2") (pin "P$67") (pinfunction "PC9_P$67") (pintype "bidirectional"))
    )
    (net (code "114") (name "SD") (class "Default")
      (node (ref "R84") (pin "1") (pinfunction "1_1") (pintype "passive"))
      (node (ref "U1") (pin "13") (pinfunction "SD_13") (pintype "output"))
      (node (ref "U2") (pin "13") (pinfunction "SD_13") (pintype "output"))
      (node (ref "U3") (pin "13") (pinfunction "SD_13") (pintype "output"))
    )
    (net (code "115") (name "SD1") (class "Default")
      (node (ref "U$2") (pin "P$87") (pinfunction "PC10_P$87") (pintype "bidirectional"))
    )
    (net (code "116") (name "SENS1") (class "Default")
      (node (ref "C61") (pin "1") (pinfunction "1_1") (pintype "passive"))
      (node (ref "R105") (pin "P$1") (pinfunction "1_P$1") (pintype "passive"))
      (node (ref "U$2") (pin "P$16") (pinfunction "PA2_P$16") (pintype "bidirectional"))
    )
    (net (code "117") (name "SENS2") (class "Default")
      (node (ref "C49") (pin "1") (pinfunction "1_1") (pintype "passive"))
      (node (ref "R104") (pin "P$1") (pinfunction "1_P$1") (pintype "passive"))
      (node (ref "U$2") (pin "P$15") (pinfunction "PA1_P$15") (pintype "bidirectional"))
    )
    (net (code "118") (name "SENS3") (class "Default")
      (node (ref "C9") (pin "1") (pinfunction "1_1") (pintype "passive"))
      (node (ref "R103") (pin "P$1") (pinfunction "1_P$1") (pintype "passive"))
      (node (ref "U$2") (pin "P$14") (pinfunction "PA0_P$14") (pintype "bidirectional"))
    )
    (net (code "119") (name "TEMP") (class "Default")
      (node (ref "C20") (pin "2") (pinfunction "2_2") (pintype "passive"))
      (node (ref "JP5") (pin "2") (pinfunction "2_2") (pintype "passive"))
      (node (ref "R61") (pin "2") (pinfunction "2_2") (pintype "passive"))
      (node (ref "U$2") (pin "P$26") (pinfunction "PA3_P$26") (pintype "bidirectional"))
    )
    (net (code "120") (name "TEMP_IN") (class "Default")
      (node (ref "C32") (pin "2") (pinfunction "2_2") (pintype "passive"))
      (node (ref "R20") (pin "1") (pinfunction "1_1") (pintype "passive"))
      (node (ref "U$2") (pin "P$8") (pinfunction "PC0_P$8") (pintype "bidirectional"))
    )
    (net (code "121") (name "TPS") (class "Default")
      (node (ref "C16") (pin "2") (pinfunction "2_2") (pintype "passive"))
      (node (ref "JP3") (pin "2") (pinfunction "2_2") (pintype "passive"))
      (node (ref "R21") (pin "2") (pinfunction "2_2") (pintype "passive"))
    )
    (net (code "122") (name "VCC") (class "Default")
      (node (ref "C22") (pin "2") (pinfunction "2_2") (pintype "passive"))
      (node (ref "C27") (pin "1") (pinfunction "1_1") (pintype "passive"))
      (node (ref "C28") (pin "1") (pinfunction "1_1") (pintype "passive"))
      (node (ref "C38") (pin "1") (pinfunction "1_1") (pintype "passive"))
      (node (ref "C58") (pin "1") (pinfunction "1_1") (pintype "passive"))
      (node (ref "C59") (pin "1") (pinfunction "1_1") (pintype "passive"))
      (node (ref "C63") (pin "+") (pinfunction "+_+") (pintype "passive"))
      (node (ref "C69") (pin "2") (pinfunction "2_2") (pintype "passive"))
      (node (ref "C77") (pin "1") (pinfunction "1_1") (pintype "passive"))
      (node (ref "C78") (pin "1") (pinfunction "1_1") (pintype "passive"))
      (node (ref "D7") (pin "2") (pinfunction "C_2") (pintype "passive"))
      (node (ref "D8") (pin "2") (pinfunction "C_2") (pintype "passive"))
      (node (ref "D9") (pin "2") (pinfunction "C_2") (pintype "passive"))
      (node (ref "JP1") (pin "1") (pinfunction "1_1") (pintype "passive"))
      (node (ref "JP2") (pin "1") (pinfunction "1_1") (pintype "passive"))
      (node (ref "JP3") (pin "3") (pinfunction "3_3") (pintype "passive"))
      (node (ref "JP5") (pin "1") (pinfunction "1_1") (pintype "passive"))
      (node (ref "R18") (pin "2") (pinfunction "2_2") (pintype "passive"))
      (node (ref "R40") (pin "2") (pinfunction "2_2") (pintype "passive"))
      (node (ref "R47") (pin "2") (pinfunction "2_2") (pintype "passive"))
      (node (ref "R49") (pin "2") (pinfunction "2_2") (pintype "passive"))
      (node (ref "R58") (pin "1") (pinfunction "1_1") (pintype "passive"))
      (node (ref "R60") (pin "1") (pinfunction "1_1") (pintype "passive"))
      (node (ref "R64") (pin "1") (pinfunction "1_1") (pintype "passive"))
      (node (ref "U$2") (pin "P$1") (pinfunction "VBATT_P$1") (pintype "bidirectional"))
      (node (ref "U$2") (pin "P$100") (pinfunction "VDD1_P$100") (pintype "bidirectional"))
      (node (ref "U$2") (pin "P$13") (pinfunction "VDDA_P$13") (pintype "bidirectional"))
      (node (ref "U$2") (pin "P$28") (pinfunction "VDD4_P$28") (pintype "bidirectional"))
      (node (ref "U$2") (pin "P$41") (pinfunction "VDD2_P$41") (pintype "bidirectional"))
      (node (ref "U$2") (pin "P$75") (pinfunction "VDD3_P$75") (pintype "bidirectional"))
      (node (ref "U$20") (pin "3") (pinfunction "VCC_3") (pintype "bidirectional"))
      (node (ref "U$21") (pin "3") (pinfunction "VCC_3") (pintype "bidirectional"))
      (node (ref "U11") (pin "4") (pinfunction "OUT_4") (pintype "passive"))
    )
    (net (code "123") (name "unconnected-(U$2-PA4-PadP$29)") (class "Default")
      (node (ref "U$2") (pin "P$29") (pinfunction "PA4_P$29") (pintype "bidirectional"))
    )
    (net (code "124") (name "unconnected-(U$2-PA5-PadP$30)") (class "Default")
      (node (ref "U$2") (pin "P$30") (pinfunction "PA5_P$30") (pintype "bidirectional"))
    )
    (net (code "125") (name "unconnected-(U$2-PA7-PadP$32)") (class "Default")
      (node (ref "U$2") (pin "P$32") (pinfunction "PA7_P$32") (pintype "bidirectional"))
    )
    (net (code "126") (name "unconnected-(U$2-PA15-PadP$86)") (class "Default")
      (node (ref "U$2") (pin "P$86") (pinfunction "PA15_P$86") (pintype "bidirectional"))
    )
    (net (code "127") (name "unconnected-(U$2-PB2-PadP$37)") (class "Default")
      (node (ref "U$2") (pin "P$37") (pinfunction "PB2_P$37") (pintype "bidirectional"))
    )
    (net (code "128") (name "unconnected-(U$2-PB3-PadP$91)") (class "Default")
      (node (ref "U$2") (pin "P$91") (pinfunction "PB3_P$91") (pintype "bidirectional"))
    )
    (net (code "129") (name "unconnected-(U$2-PB5-PadP$93)") (class "Default")
      (node (ref "U$2") (pin "P$93") (pinfunction "PB5_P$93") (pintype "bidirectional"))
    )
    (net (code "130") (name "unconnected-(U$2-PB12-PadP$60)") (class "Default")
      (node (ref "U$2") (pin "P$60") (pinfunction "PB12_P$60") (pintype "bidirectional"))
    )
    (net (code "131") (name "unconnected-(U$2-PC1-PadP$9)") (class "Default")
      (node (ref "U$2") (pin "P$9") (pinfunction "PC1_P$9") (pintype "bidirectional"))
    )
    (net (code "132") (name "unconnected-(U$2-PC3-PadP$11)") (class "Default")
      (node (ref "U$2") (pin "P$11") (pinfunction "PC3_P$11") (pintype "bidirectional"))
    )
    (net (code "133") (name "unconnected-(U$2-PC8-PadP$66)") (class "Default")
      (node (ref "U$2") (pin "P$66") (pinfunction "PC8_P$66") (pintype "bidirectional"))
    )
    (net (code "134") (name "unconnected-(U$2-PC13-PadP$2)") (class "Default")
      (node (ref "U$2") (pin "P$2") (pinfunction "PC13_P$2") (pintype "bidirectional"))
    )
    (net (code "135") (name "unconnected-(U$2-PC14-PadP$3)") (class "Default")
      (node (ref "U$2") (pin "P$3") (pinfunction "PC14_P$3") (pintype "bidirectional"))
    )
    (net (code "136") (name "unconnected-(U$2-PC15-PadP$4)") (class "Default")
      (node (ref "U$2") (pin "P$4") (pinfunction "PC15_P$4") (pintype "bidirectional"))
    )
    (net (code "137") (name "unconnected-(U$2-PD2-PadP$90)") (class "Default")
      (node (ref "U$2") (pin "P$90") (pinfunction "PD2_P$90") (pintype "bidirectional"))
    )
    (net (code "138") (name "unconnected-(U1-NC1-Pad4)") (class "Default")
      (node (ref "U1") (pin "4") (pinfunction "NC1_4") (pintype "input"))
    )
    (net (code "139") (name "unconnected-(U1-NC2-Pad5)") (class "Default")
      (node (ref "U1") (pin "5") (pinfunction "NC2_5") (pintype "output"))
    )
    (net (code "140") (name "unconnected-(U1-NC3-Pad9)") (class "Default")
      (node (ref "U1") (pin "9") (pinfunction "NC3_9") (pintype "input"))
    )
    (net (code "141") (name "unconnected-(U1-NC4-Pad10)") (class "Default")
      (node (ref "U1") (pin "10") (pinfunction "NC4_10") (pintype "output"))
    )
    (net (code "142") (name "unconnected-(U1-NC5-Pad16)") (class "Default")
      (node (ref "U1") (pin "16") (pinfunction "NC5_16") (pintype "bidirectional"))
    )
    (net (code "143") (name "unconnected-(U2-NC1-Pad4)") (class "Default")
      (node (ref "U2") (pin "4") (pinfunction "NC1_4") (pintype "input"))
    )
    (net (code "144") (name "unconnected-(U2-NC2-Pad5)") (class "Default")
      (node (ref "U2") (pin "5") (pinfunction "NC2_5") (pintype "output"))
    )
    (net (code "145") (name "unconnected-(U2-NC3-Pad9)") (class "Default")
      (node (ref "U2") (pin "9") (pinfunction "NC3_9") (pintype "input"))
    )
    (net (code "146") (name "unconnected-(U2-NC4-Pad10)") (class "Default")
      (node (ref "U2") (pin "10") (pinfunction "NC4_10") (pintype "output"))
    )
    (net (code "147") (name "unconnected-(U2-NC5-Pad16)") (class "Default")
      (node (ref "U2") (pin "16") (pinfunction "NC5_16") (pintype "bidirectional"))
    )
    (net (code "148") (name "unconnected-(U3-NC1-Pad4)") (class "Default")
      (node (ref "U3") (pin "4") (pinfunction "NC1_4") (pintype "input"))
    )
    (net (code "149") (name "unconnected-(U3-NC2-Pad5)") (class "Default")
      (node (ref "U3") (pin "5") (pinfunction "NC2_5") (pintype "output"))
    )
    (net (code "150") (name "unconnected-(U3-NC3-Pad9)") (class "Default")
      (node (ref "U3") (pin "9") (pinfunction "NC3_9") (pintype "input"))
    )
    (net (code "151") (name "unconnected-(U3-NC4-Pad10)") (class "Default")
      (node (ref "U3") (pin "10") (pinfunction "NC4_10") (pintype "output"))
    )
    (net (code "152") (name "unconnected-(U3-NC5-Pad16)") (class "Default")
      (node (ref "U3") (pin "16") (pinfunction "NC5_16") (pintype "bidirectional"))
    )
    (net (code "153") (name "unconnected-(U73-VREF-PadP$5)") (class "Default")
      (node (ref "U73") (pin "P$5") (pinfunction "VREF_P$5") (pintype "bidirectional"))
    )
    (net (code "154") (name "unconnected-(USB2-Pad1)") (class "Default")
      (node (ref "USB2") (pin "1") (pinfunction "1_1") (pintype "passive"))
    )
    (net (code "155") (name "unconnected-(USB2-Pad4)") (class "Default")
      (node (ref "USB2") (pin "4") (pinfunction "4_4") (pintype "passive"))
    )
  )
)
